# NIPCB.net
KiCad netlist of a schematic drawn in EAGLE
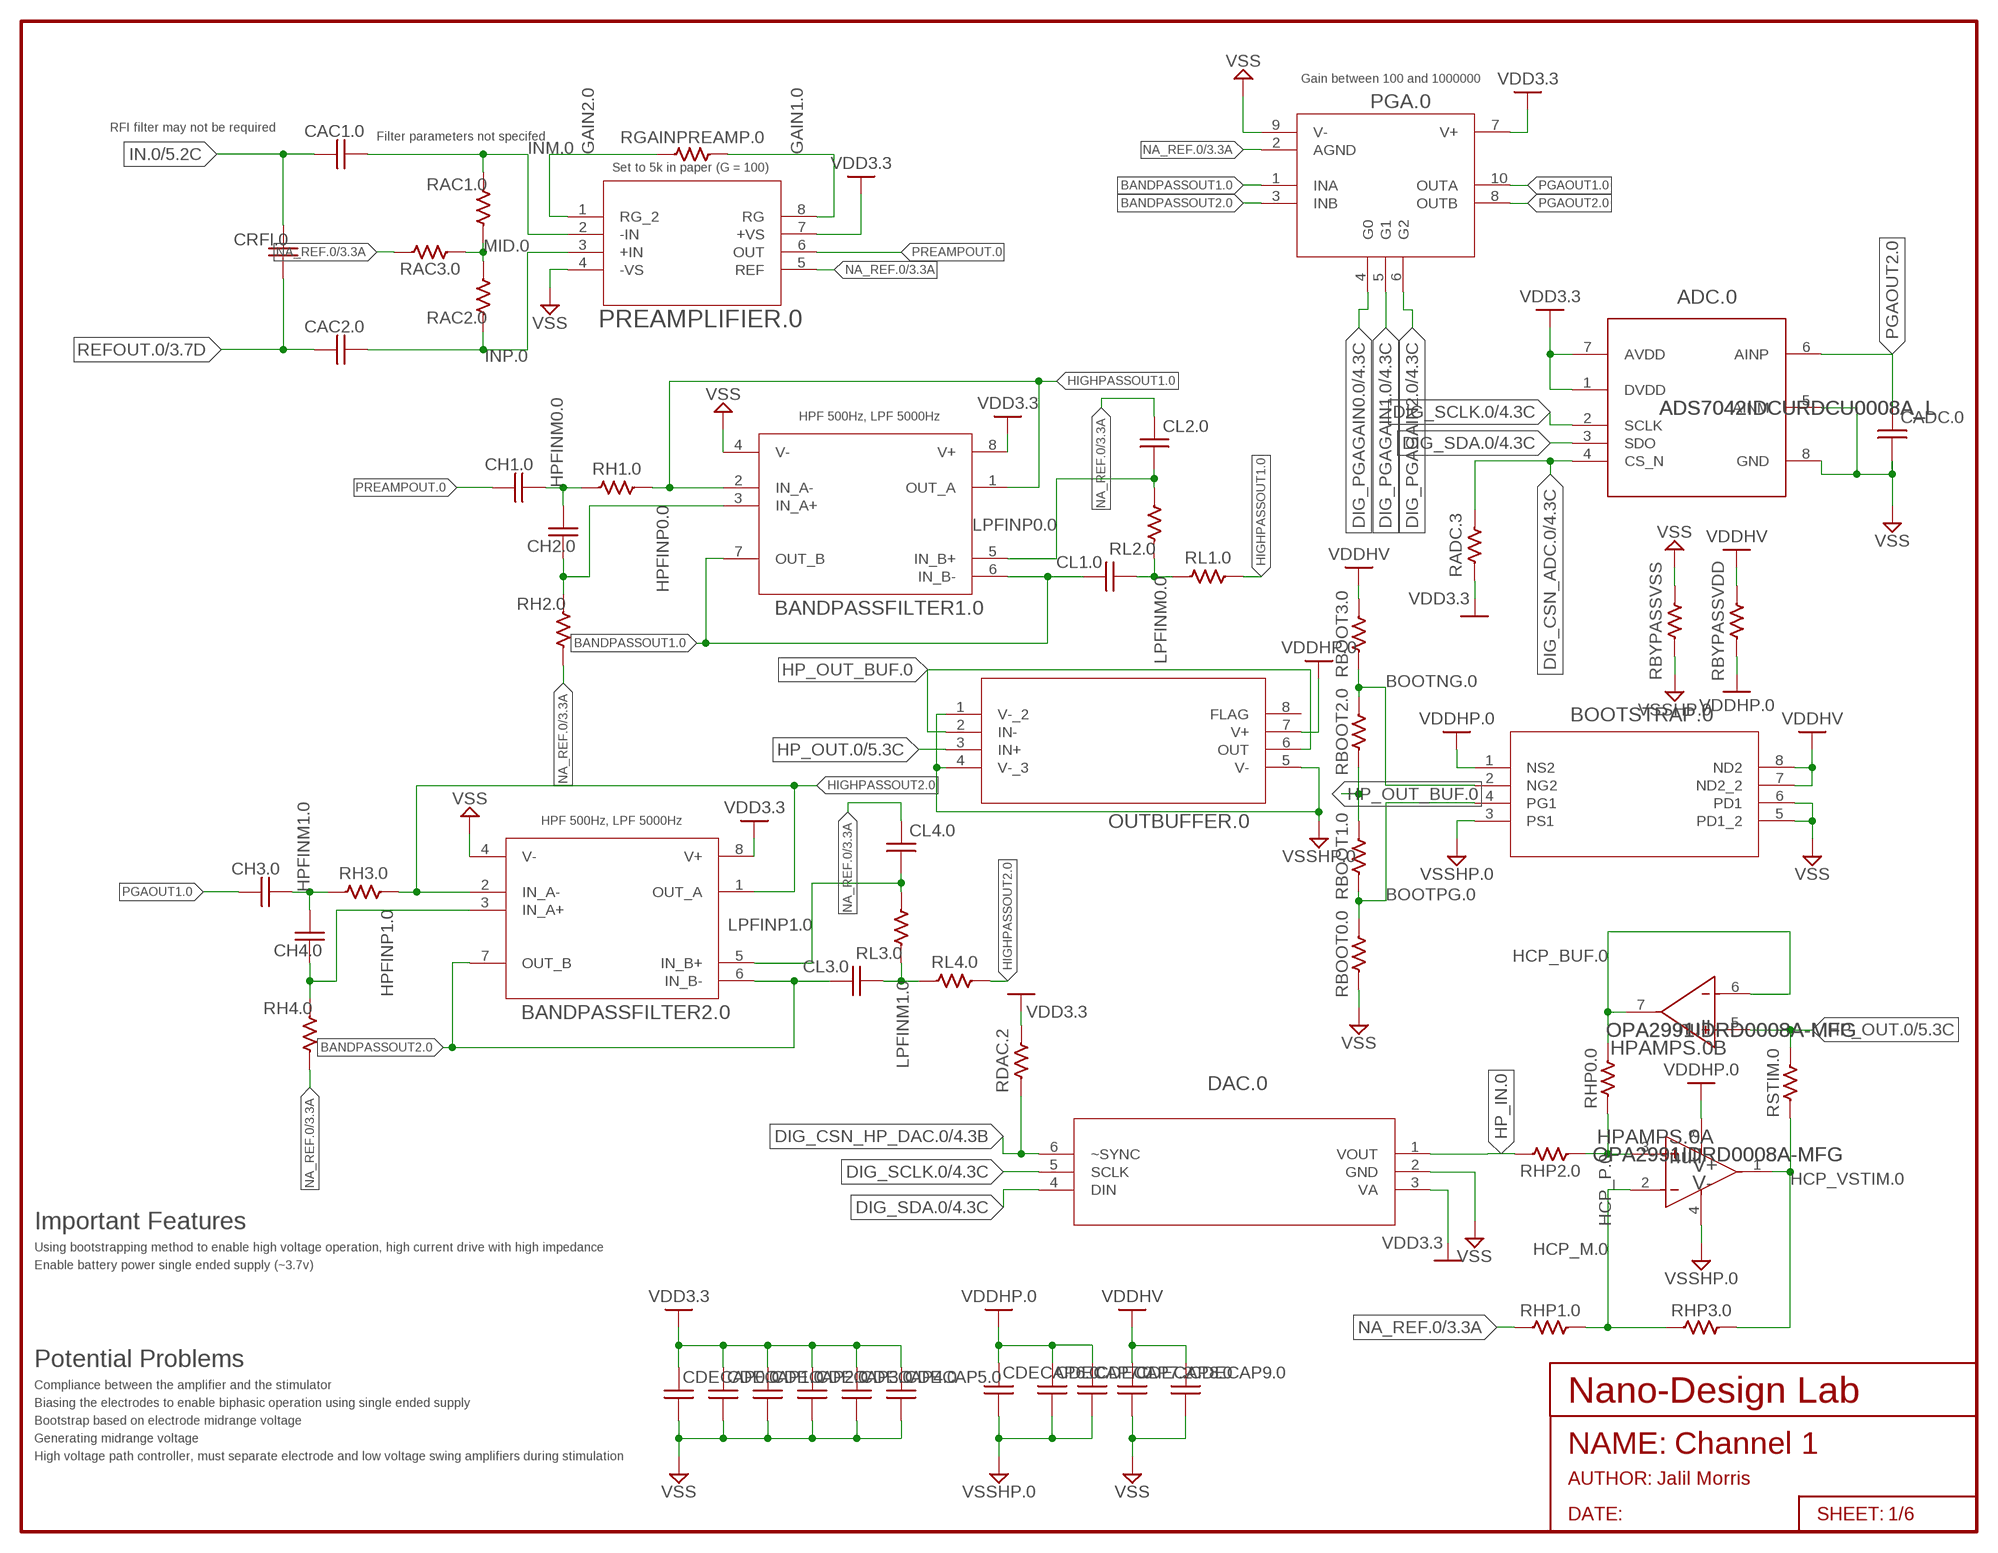
[diagram p0: schematic, sheet 1]
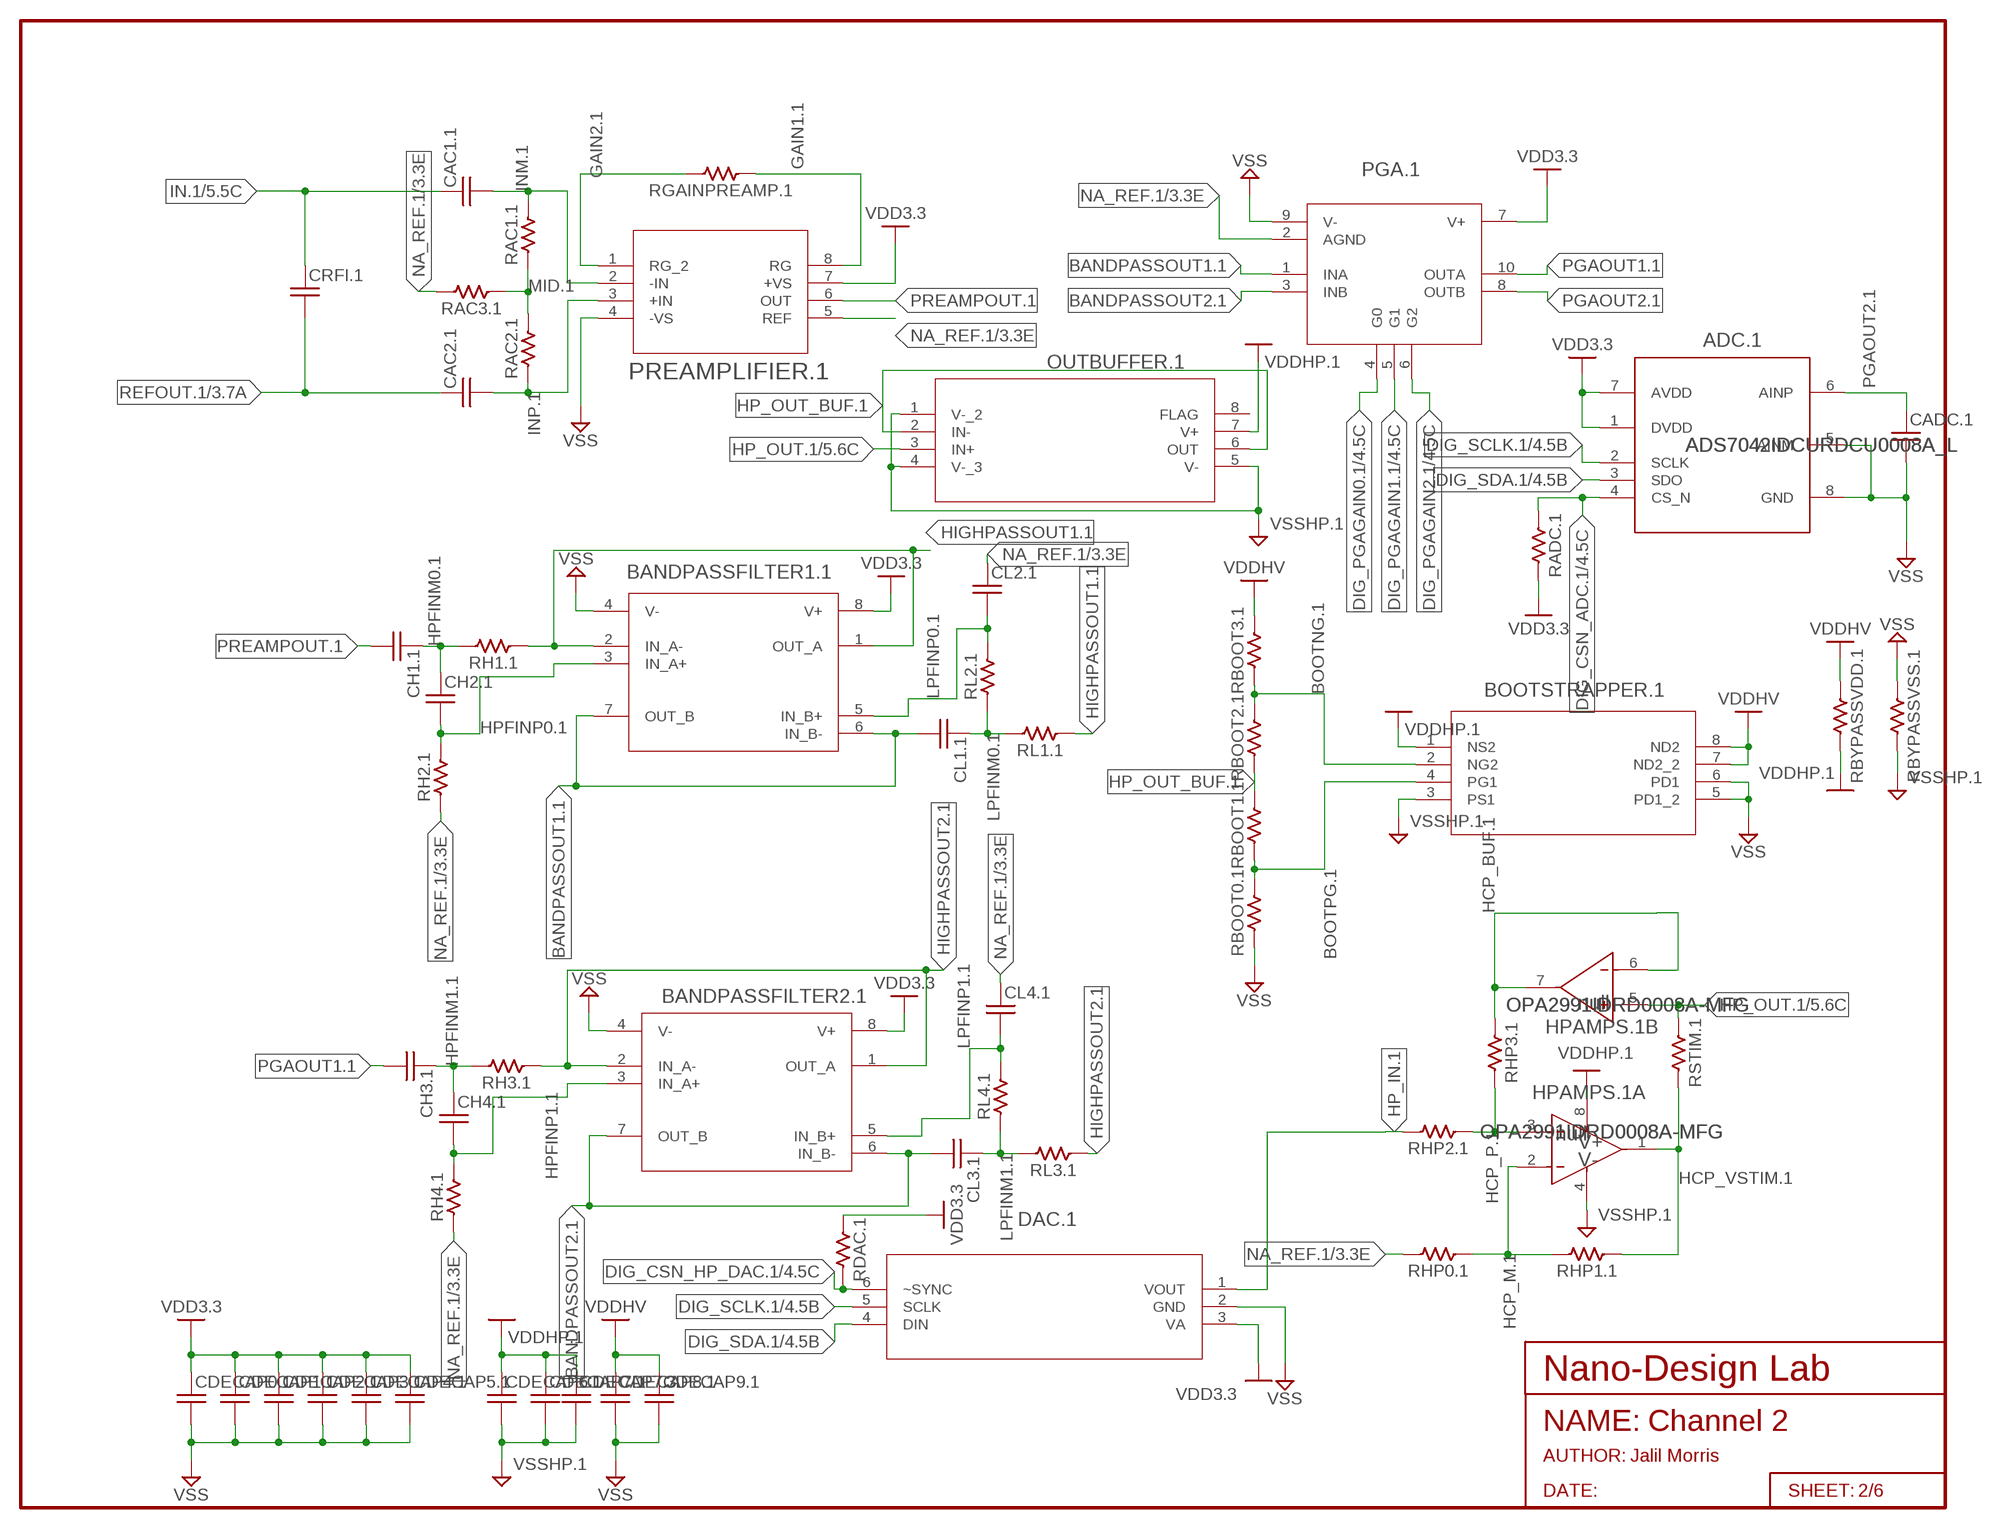
[diagram p1: schematic, sheet 2]
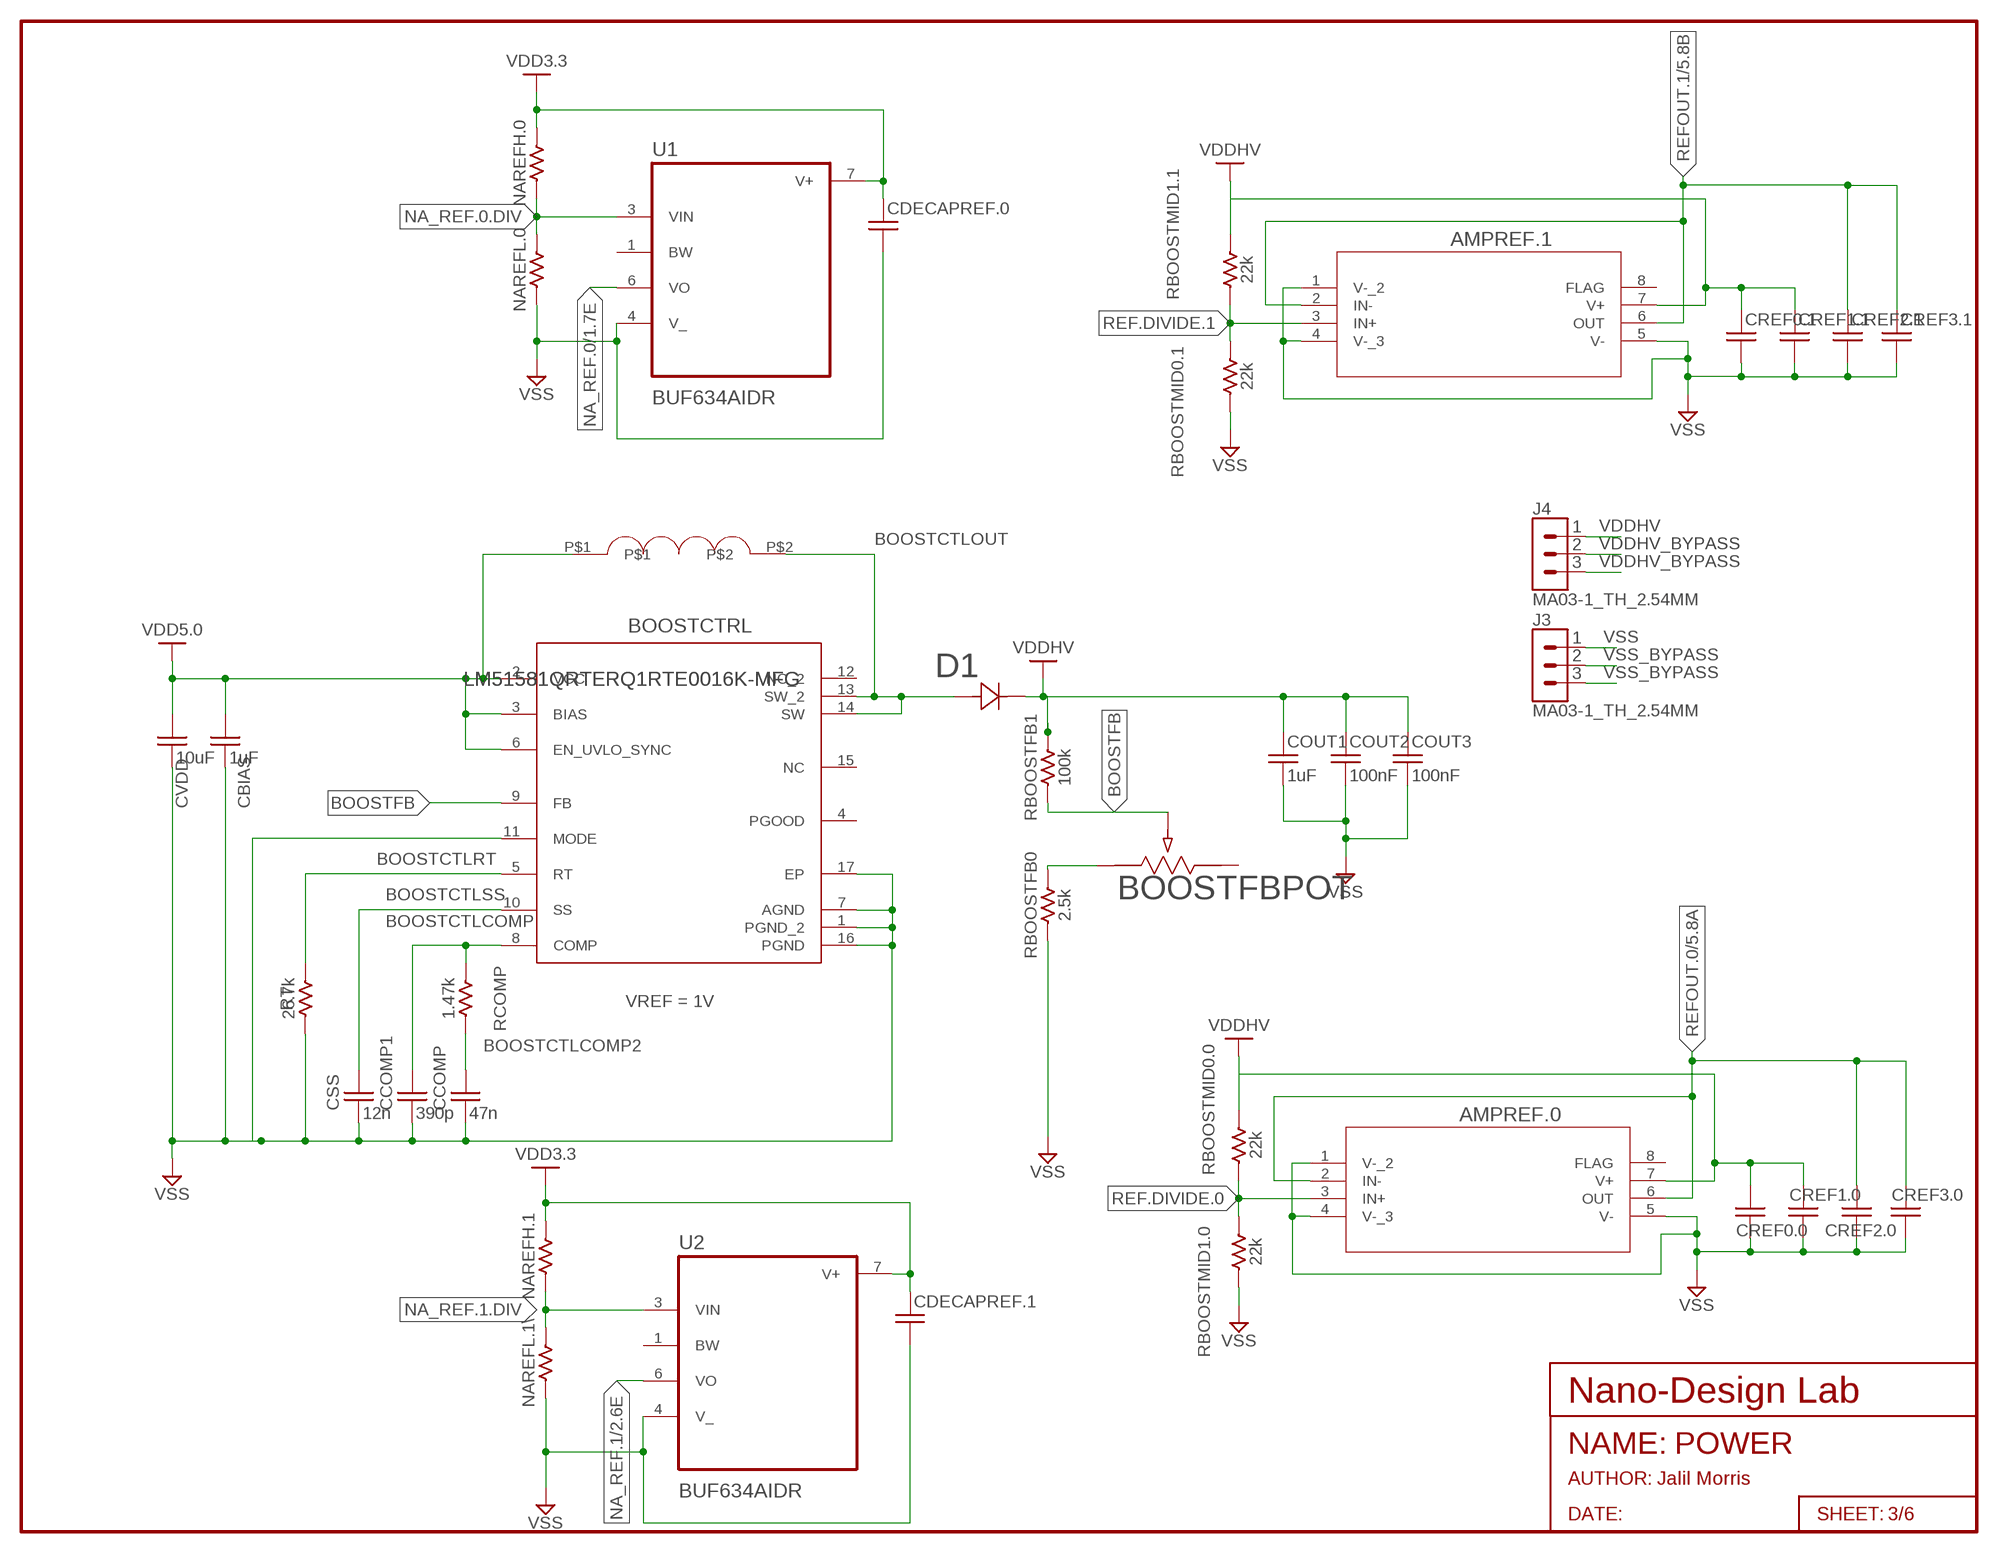
[diagram p2: schematic, sheet 3]
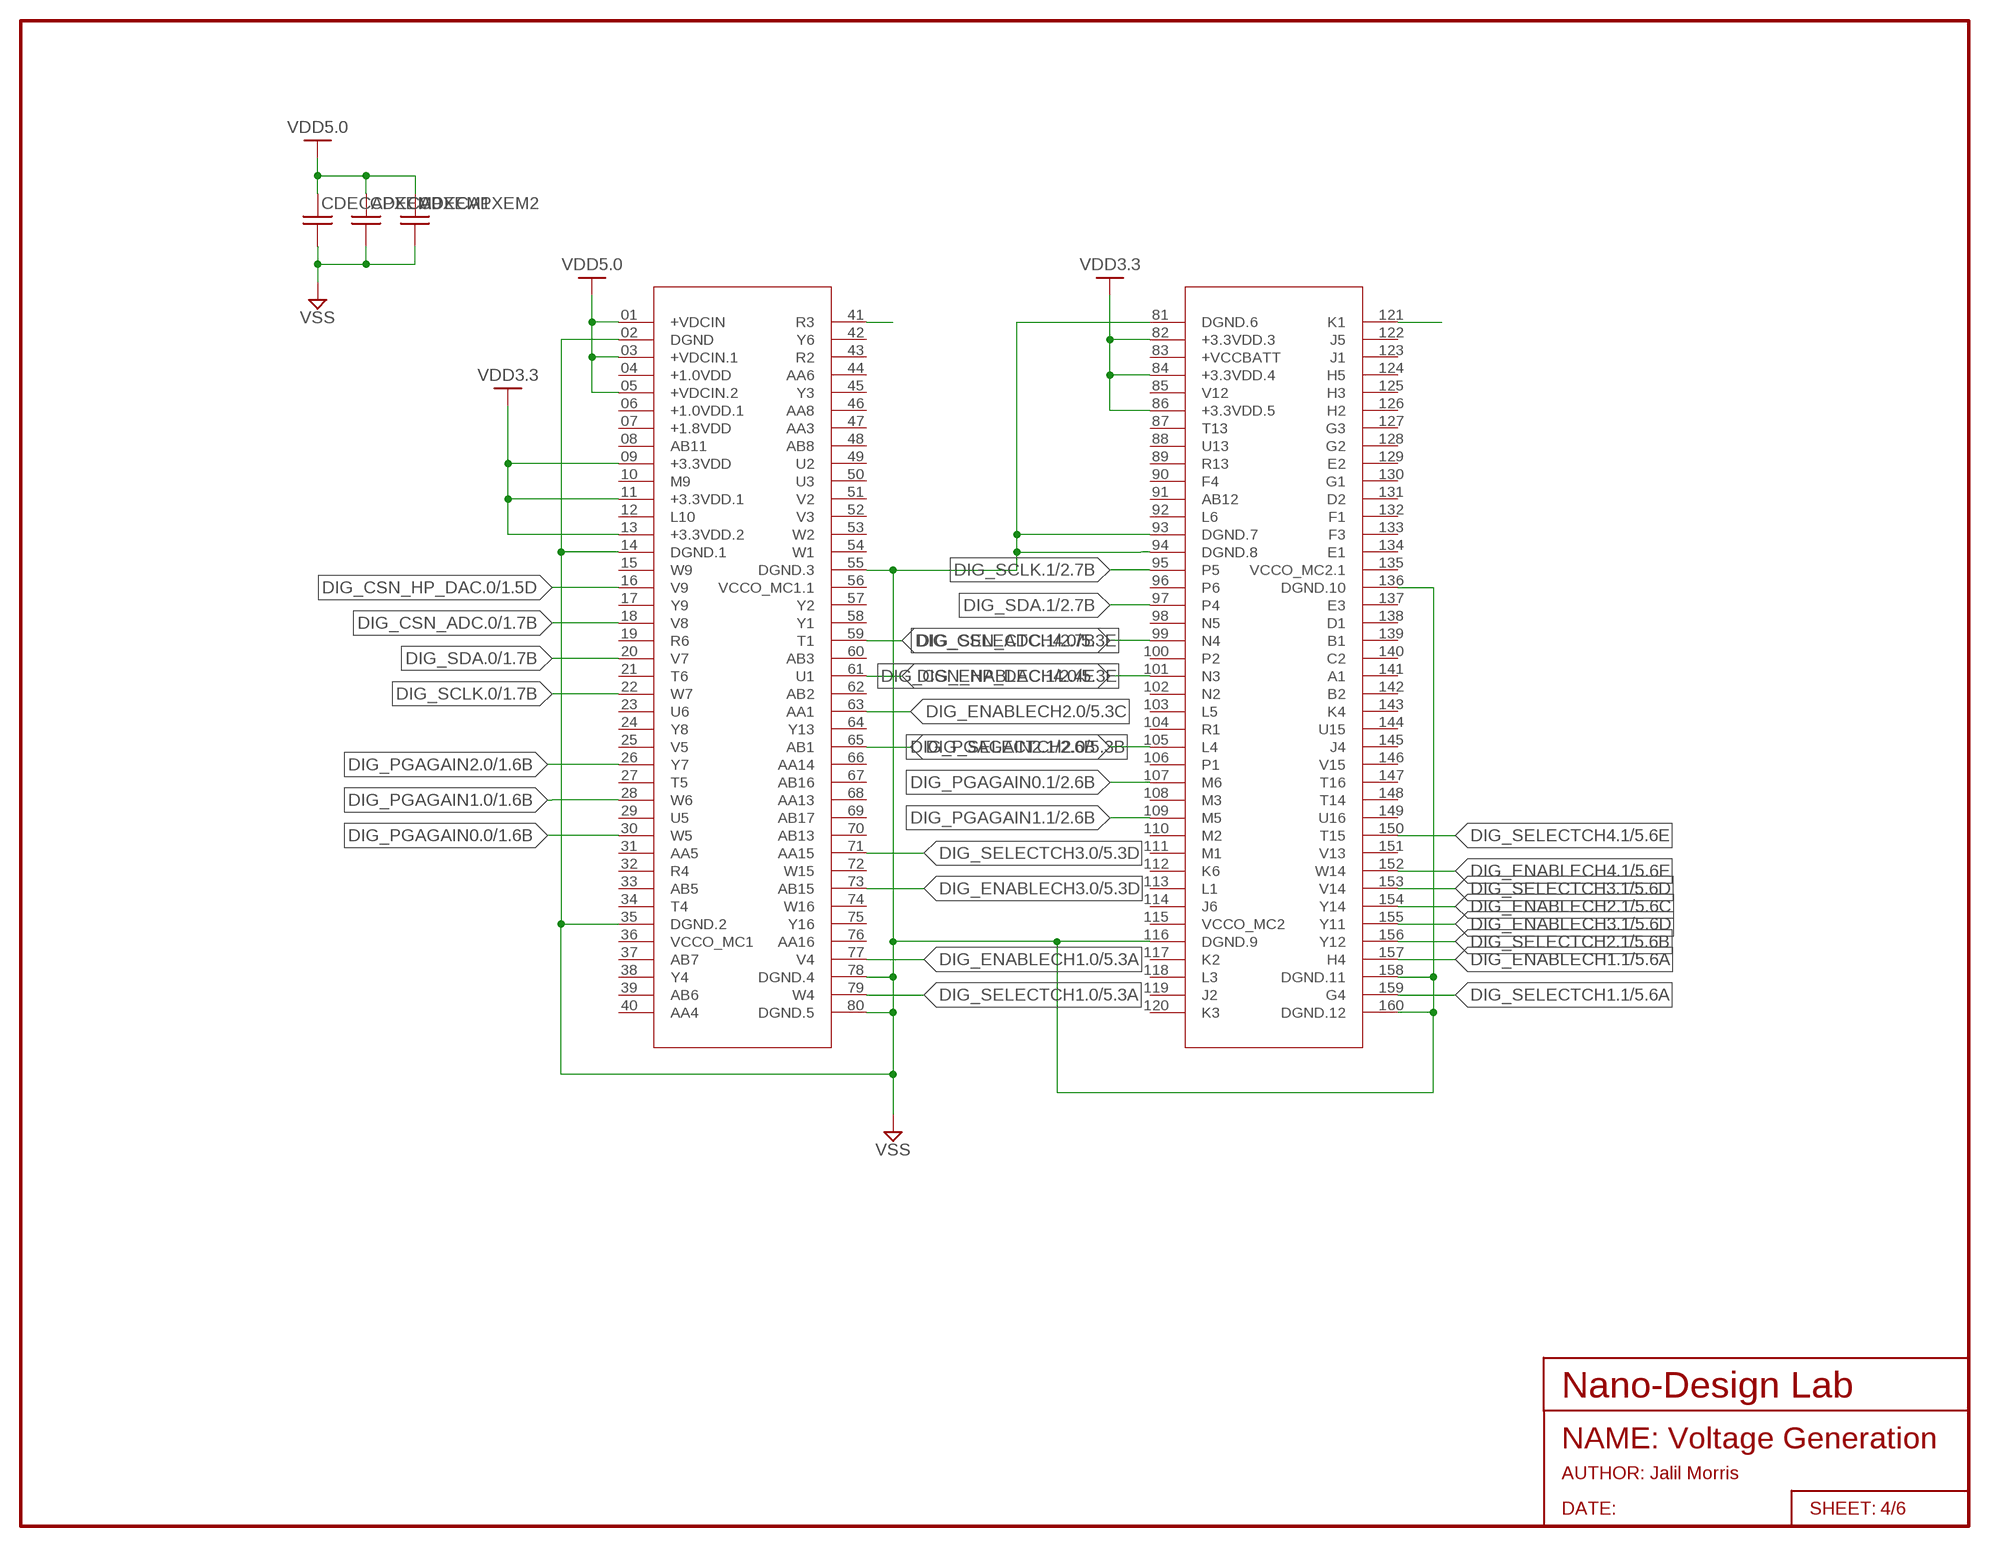
[diagram p3: schematic, sheet 4]
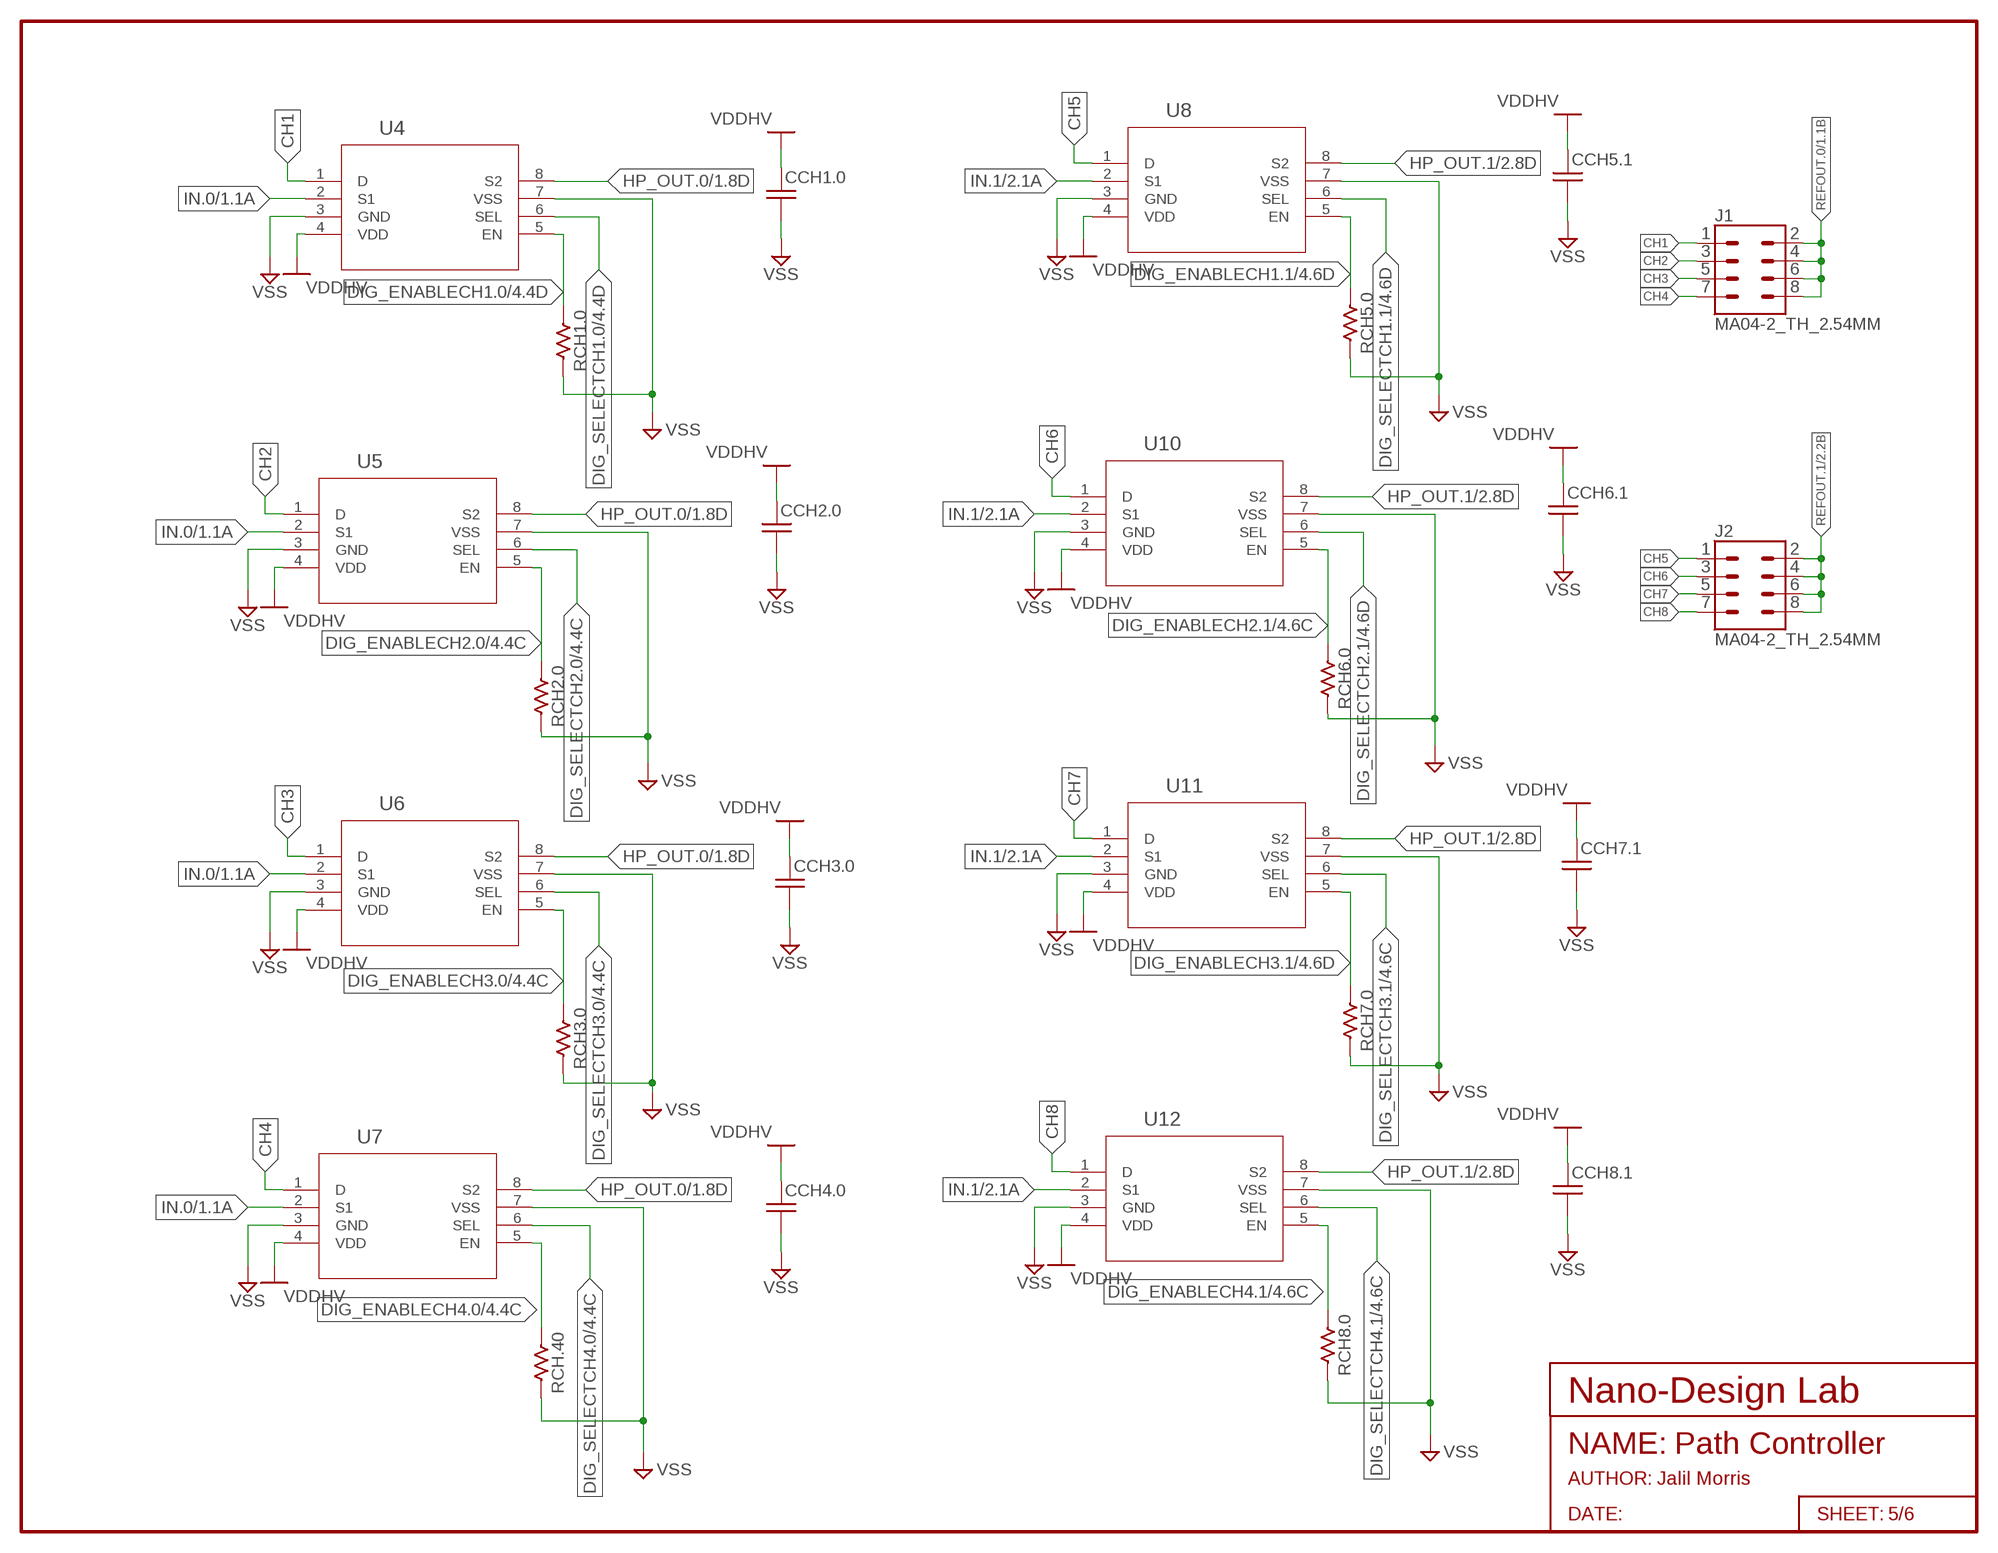
[diagram p4: schematic, sheet 5]
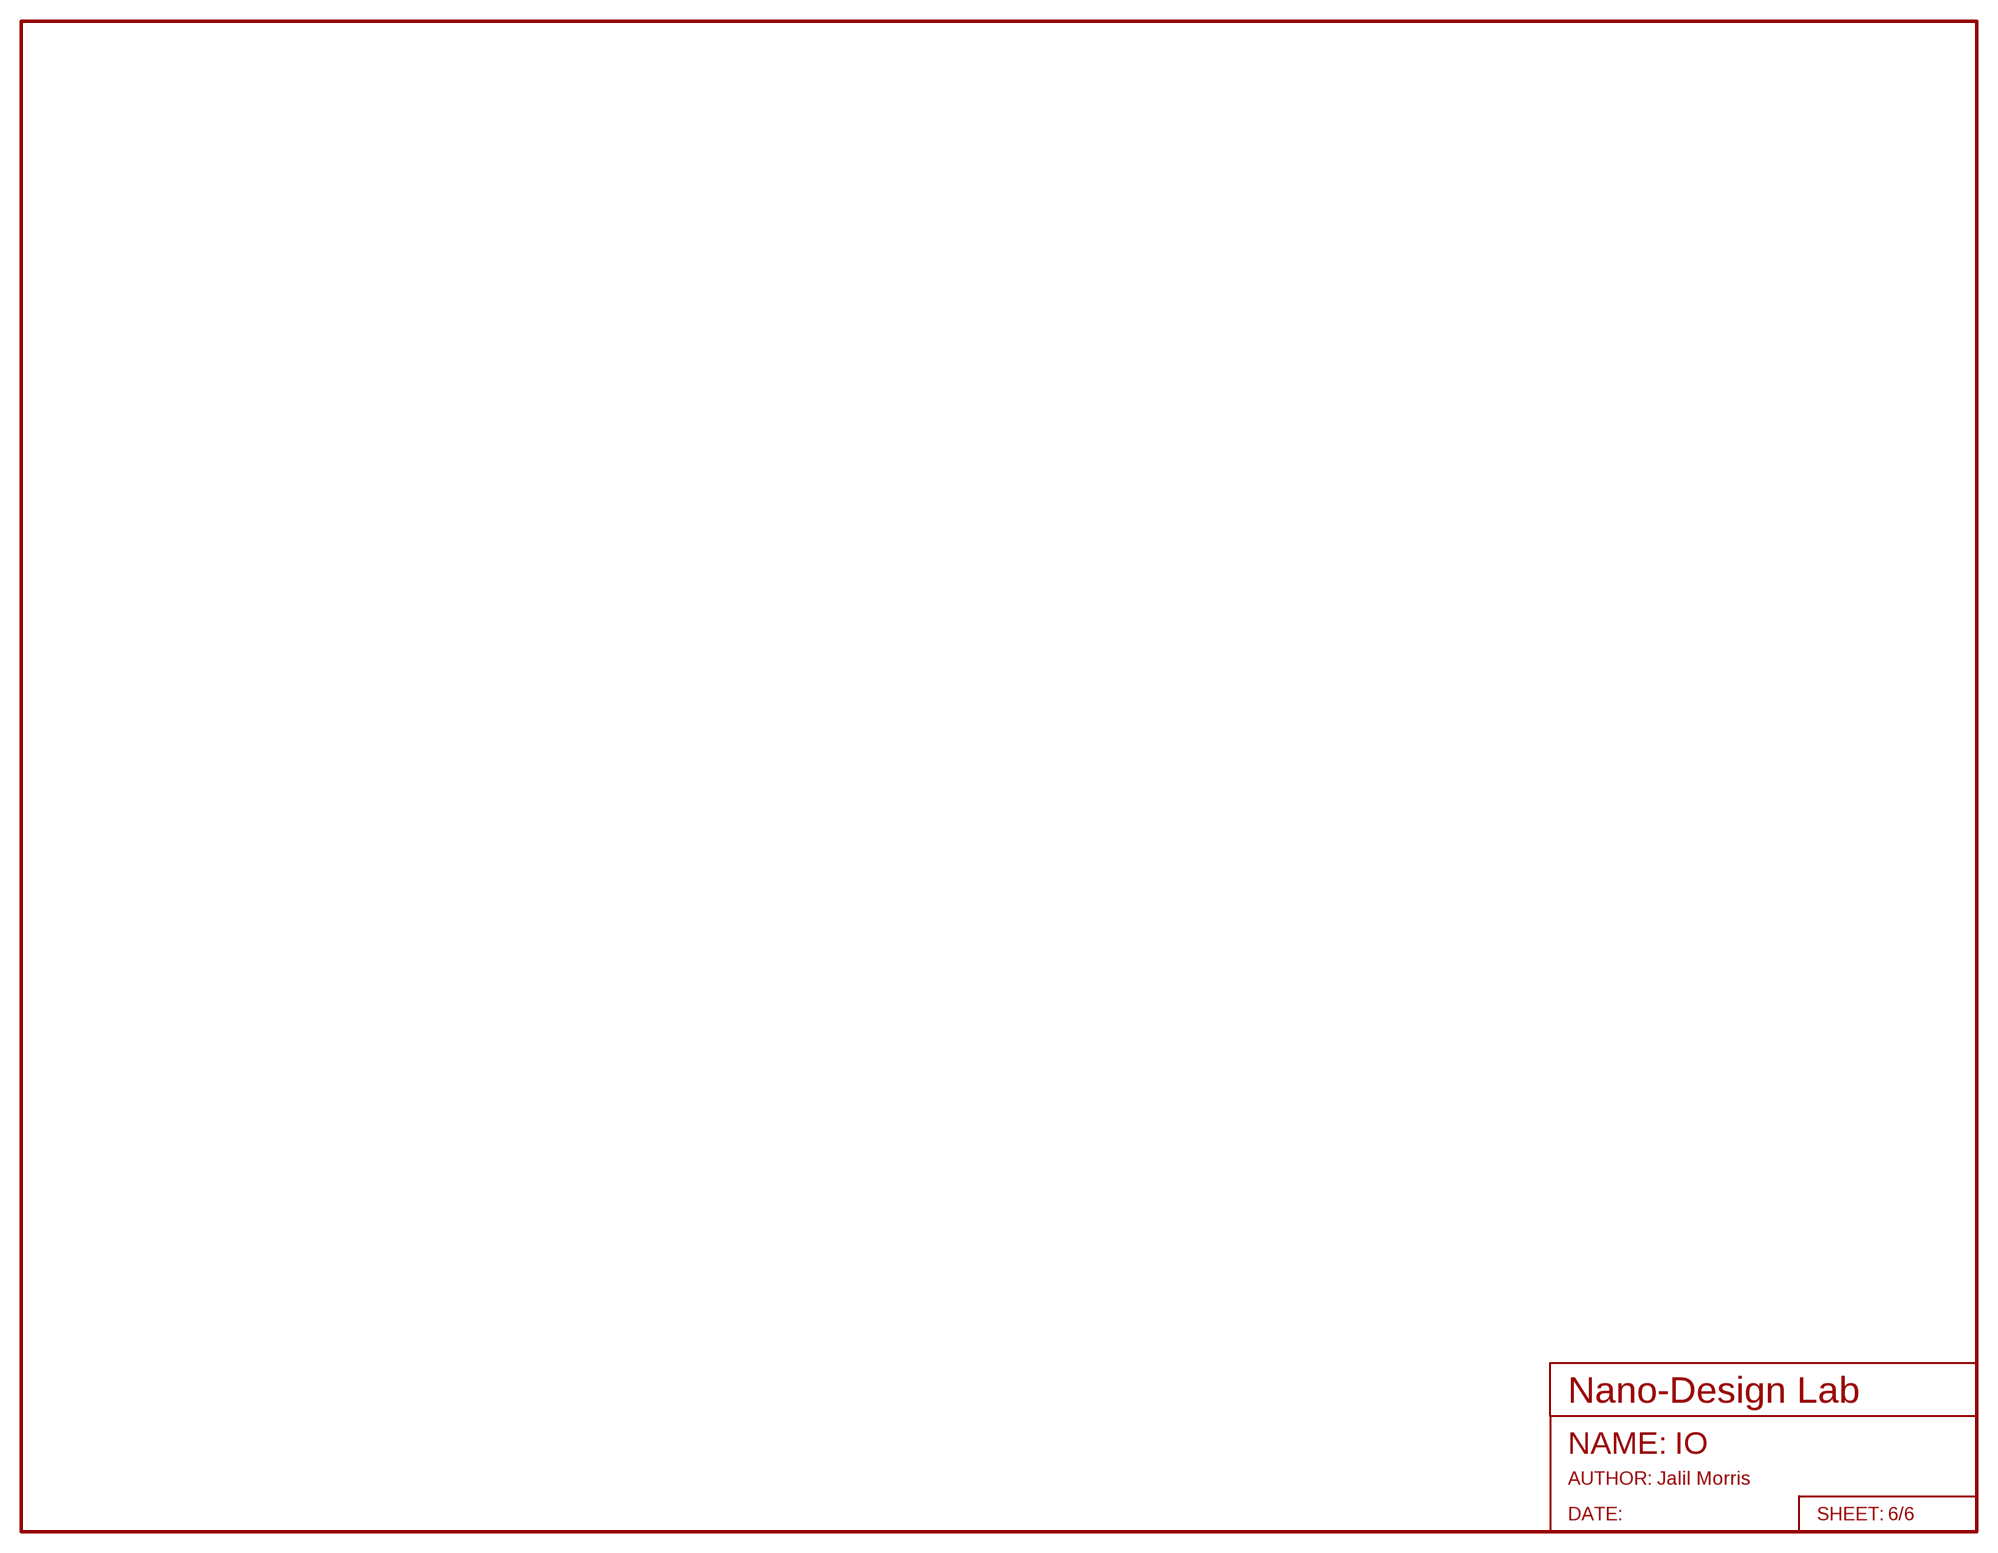
[diagram p5: schematic, sheet 6]

(export (version "E")
  (design (tool "Eeschema 10.0.6"))
  (components
    (comp (ref "ADC.0")
      (value "ADS7042IDCURDCU0008A_L")
      (footprint "eagle-import:DCU0008A_L")
      (fields
        (field (name "MANUFACTURER_PART_NUMBER") "ADS7042IDCUR")
        (field (name "COPYRIGHT") "Copyright (C) 2024 Ultra Librarian. All rights reserved.")
      )
      (libsource (lib "eagle-import") (part "ADS7042IDCURDCU0008A_L"))
    )
    (comp (ref "BANDPASSFILTER1.0")
      (value "OPA2325IDRD8_TEX")
      (footprint "eagle-import:D8_TEX")
      (fields
        (field (name "MANUFACTURER_PART_NUMBER") "OPA2325IDR")
        (field (name "COPYRIGHT") "Copyright (C) 2024 Ultra Librarian. All rights reserved.")
      )
      (libsource (lib "eagle-import") (part "OPA2325IDRD8_TEX"))
    )
    (comp (ref "BANDPASSFILTER2.0")
      (value "OPA2325IDRD8_TEX")
      (footprint "eagle-import:D8_TEX")
      (fields
        (field (name "MANUFACTURER_PART_NUMBER") "OPA2325IDR")
        (field (name "COPYRIGHT") "Copyright (C) 2024 Ultra Librarian. All rights reserved.")
      )
      (libsource (lib "eagle-import") (part "OPA2325IDRD8_TEX"))
    )
    (comp (ref "BOOTSTRAP.0")
      (value "DMC4047LSD-13SO8_DIO")
      (footprint "eagle-import:SO8_DIO")
      (fields
        (field (name "MANUFACTURER_PART_NUMBER") "DMC4047LSD-13")
        (field (name "COPYRIGHT") "Copyright (C) 2024 Ultra Librarian. All rights reserved.")
      )
      (libsource (lib "eagle-import") (part "DMC4047LSD-13SO8_DIO"))
    )
    (comp (ref "CAC1.0")
      (value "C-US0402")
      (footprint "eagle-import:0402")
      (libsource (lib "eagle-import") (part "C-US0402"))
    )
    (comp (ref "CAC2.0")
      (value "C-US0402")
      (footprint "eagle-import:0402")
      (libsource (lib "eagle-import") (part "C-US0402"))
    )
    (comp (ref "CADC.0")
      (value "C-US0402")
      (footprint "eagle-import:0402")
      (libsource (lib "eagle-import") (part "C-US0402"))
    )
    (comp (ref "CDECAP0.0")
      (value "C-US0402")
      (footprint "eagle-import:0402")
      (libsource (lib "eagle-import") (part "C-US0402"))
    )
    (comp (ref "CDECAP1.0")
      (value "C-US0402")
      (footprint "eagle-import:0402")
      (libsource (lib "eagle-import") (part "C-US0402"))
    )
    (comp (ref "CDECAP2.0")
      (value "C-US0402")
      (footprint "eagle-import:0402")
      (libsource (lib "eagle-import") (part "C-US0402"))
    )
    (comp (ref "CDECAP3.0")
      (value "C-US0402")
      (footprint "eagle-import:0402")
      (libsource (lib "eagle-import") (part "C-US0402"))
    )
    (comp (ref "CDECAP4.0")
      (value "C-US0402")
      (footprint "eagle-import:0402")
      (libsource (lib "eagle-import") (part "C-US0402"))
    )
    (comp (ref "CDECAP5.0")
      (value "C-US0402")
      (footprint "eagle-import:0402")
      (libsource (lib "eagle-import") (part "C-US0402"))
    )
    (comp (ref "CDECAP6.0")
      (value "C-US0402")
      (footprint "eagle-import:0402")
      (libsource (lib "eagle-import") (part "C-US0402"))
    )
    (comp (ref "CDECAP7.0")
      (value "C-US0402")
      (footprint "eagle-import:0402")
      (libsource (lib "eagle-import") (part "C-US0402"))
    )
    (comp (ref "CDECAP7.2")
      (value "C-US0402")
      (footprint "eagle-import:0402")
      (libsource (lib "eagle-import") (part "C-US0402"))
    )
    (comp (ref "CDECAP8.0")
      (value "C-US0402")
      (footprint "eagle-import:0402")
      (libsource (lib "eagle-import") (part "C-US0402"))
    )
    (comp (ref "CDECAP9.0")
      (value "C-US0402")
      (footprint "eagle-import:0402")
      (libsource (lib "eagle-import") (part "C-US0402"))
    )
    (comp (ref "CH1.0")
      (value "C-US0402")
      (footprint "eagle-import:0402")
      (libsource (lib "eagle-import") (part "C-US0402"))
    )
    (comp (ref "CH2.0")
      (value "C-US0402")
      (footprint "eagle-import:0402")
      (libsource (lib "eagle-import") (part "C-US0402"))
    )
    (comp (ref "CH3.0")
      (value "C-US0402")
      (footprint "eagle-import:0402")
      (libsource (lib "eagle-import") (part "C-US0402"))
    )
    (comp (ref "CH4.0")
      (value "C-US0402")
      (footprint "eagle-import:0402")
      (libsource (lib "eagle-import") (part "C-US0402"))
    )
    (comp (ref "CL1.0")
      (value "C-US0402")
      (footprint "eagle-import:0402")
      (libsource (lib "eagle-import") (part "C-US0402"))
    )
    (comp (ref "CL2.0")
      (value "C-US0402")
      (footprint "eagle-import:0402")
      (libsource (lib "eagle-import") (part "C-US0402"))
    )
    (comp (ref "CL3.0")
      (value "C-US0402")
      (footprint "eagle-import:0402")
      (libsource (lib "eagle-import") (part "C-US0402"))
    )
    (comp (ref "CL4.0")
      (value "C-US0402")
      (footprint "eagle-import:0402")
      (libsource (lib "eagle-import") (part "C-US0402"))
    )
    (comp (ref "CRFI.0")
      (value "C-US0402")
      (footprint "eagle-import:0402")
      (libsource (lib "eagle-import") (part "C-US0402"))
    )
    (comp (ref "DAC.0")
      (value "DAC081S101CIMKX/NOPBMK06A")
      (footprint "eagle-import:MK06A")
      (fields
        (field (name "MANUFACTURER_PART_NUMBER") "DAC081S101CIMKX/NOPB")
        (field (name "COPYRIGHT") "Copyright (C) 2024 Ultra Librarian. All rights reserved.")
      )
      (libsource (lib "eagle-import") (part "DAC081S101CIMKX/NOPBMK06A"))
    )
    (comp (ref "HPAMPS.0")
      (value "OPA2991IDRD0008A-MFG")
      (footprint "eagle-import:D0008A-MFG")
      (fields
        (field (name "MANUFACTURER_PART_NUMBER") "OPA2991IDR")
        (field (name "COPYRIGHT") "Copyright (C) 2024 Ultra Librarian. All rights reserved.")
      )
      (libsource (lib "eagle-import") (part "OPA2991IDRD0008A-MFG"))
    )
    (comp (ref "OUTBUFFER.0")
      (value "OPA552UA/2K5D8")
      (footprint "eagle-import:D8")
      (fields
        (field (name "MANUFACTURER_PART_NUMBER") "OPA552UA/2K5")
        (field (name "COPYRIGHT") "Copyright (C) 2024 Ultra Librarian. All rights reserved.")
      )
      (libsource (lib "eagle-import") (part "OPA552UA/2K5D8"))
    )
    (comp (ref "PGA.0")
      (value "LTC6911CMS-1TRPBFMSOP-10_MS_LIT")
      (footprint "eagle-import:MSOP-10_MS_LIT")
      (fields
        (field (name "MANUFACTURER_PART_NUMBER") "LTC6911CMS-1#TRPBF")
        (field (name "COPYRIGHT") "Copyright (C) 2024 Ultra Librarian. All rights reserved.")
      )
      (libsource (lib "eagle-import") (part "LTC6911CMS-1TRPBFMSOP-10_MS_LIT"))
    )
    (comp (ref "PREAMPLIFIER.0")
      (value "INA818IDSOIC-8_TEX")
      (footprint "eagle-import:SOIC-8_TEX")
      (fields
        (field (name "MANUFACTURER_PART_NUMBER") "INA818ID")
        (field (name "COPYRIGHT") "Copyright (C) 2024 Ultra Librarian. All rights reserved.")
      )
      (libsource (lib "eagle-import") (part "INA818IDSOIC-8_TEX"))
    )
    (comp (ref "RAC1.0")
      (value "R-US0402")
      (footprint "eagle-import:0402")
      (libsource (lib "eagle-import") (part "R-US0402"))
    )
    (comp (ref "RAC2.0")
      (value "R-US0402")
      (footprint "eagle-import:0402")
      (libsource (lib "eagle-import") (part "R-US0402"))
    )
    (comp (ref "RAC3.0")
      (value "R-US0402")
      (footprint "eagle-import:0402")
      (libsource (lib "eagle-import") (part "R-US0402"))
    )
    (comp (ref "RADC.3")
      (value "R-US0402")
      (footprint "eagle-import:0402")
      (libsource (lib "eagle-import") (part "R-US0402"))
    )
    (comp (ref "RBOOT0.0")
      (value "R-US0603")
      (footprint "eagle-import:0603")
      (libsource (lib "eagle-import") (part "esbd-passives_vf.aVnswyxgQrGgV-hLEV-kMQ_R-US0603"))
    )
    (comp (ref "RBOOT1.0")
      (value "R-US0603")
      (footprint "eagle-import:0603")
      (libsource (lib "eagle-import") (part "esbd-passives_vf.aVnswyxgQrGgV-hLEV-kMQ_R-US0603"))
    )
    (comp (ref "RBOOT2.0")
      (value "R-US0603")
      (footprint "eagle-import:0603")
      (libsource (lib "eagle-import") (part "esbd-passives_vf.aVnswyxgQrGgV-hLEV-kMQ_R-US0603"))
    )
    (comp (ref "RBOOT3.0")
      (value "R-US0603")
      (footprint "eagle-import:0603")
      (libsource (lib "eagle-import") (part "esbd-passives_vf.aVnswyxgQrGgV-hLEV-kMQ_R-US0603"))
    )
    (comp (ref "RBYPASSVDD")
      (value "R-US0402")
      (footprint "eagle-import:0402")
      (libsource (lib "eagle-import") (part "R-US0402"))
    )
    (comp (ref "RBYPASSVSS")
      (value "R-US0402")
      (footprint "eagle-import:0402")
      (libsource (lib "eagle-import") (part "R-US0402"))
    )
    (comp (ref "RDAC.2")
      (value "R-US0402")
      (footprint "eagle-import:0402")
      (libsource (lib "eagle-import") (part "R-US0402"))
    )
    (comp (ref "RGAINPREAMP.0")
      (value "R-US0402")
      (footprint "eagle-import:0402")
      (libsource (lib "eagle-import") (part "R-US0402"))
    )
    (comp (ref "RH1.0")
      (value "R-US0402")
      (footprint "eagle-import:0402")
      (libsource (lib "eagle-import") (part "R-US0402"))
    )
    (comp (ref "RH2.0")
      (value "R-US0402")
      (footprint "eagle-import:0402")
      (libsource (lib "eagle-import") (part "R-US0402"))
    )
    (comp (ref "RH3.0")
      (value "R-US0402")
      (footprint "eagle-import:0402")
      (libsource (lib "eagle-import") (part "R-US0402"))
    )
    (comp (ref "RH4.0")
      (value "R-US0402")
      (footprint "eagle-import:0402")
      (libsource (lib "eagle-import") (part "R-US0402"))
    )
    (comp (ref "RHP0.0")
      (value "R-US0603")
      (footprint "eagle-import:0603")
      (libsource (lib "eagle-import") (part "esbd-passives_vf.aVnswyxgQrGgV-hLEV-kMQ_R-US0603"))
    )
    (comp (ref "RHP1.0")
      (value "R-US0603")
      (footprint "eagle-import:0603")
      (libsource (lib "eagle-import") (part "esbd-passives_vf.aVnswyxgQrGgV-hLEV-kMQ_R-US0603"))
    )
    (comp (ref "RHP2.0")
      (value "R-US0603")
      (footprint "eagle-import:0603")
      (libsource (lib "eagle-import") (part "esbd-passives_vf.aVnswyxgQrGgV-hLEV-kMQ_R-US0603"))
    )
    (comp (ref "RHP3.0")
      (value "R-US0603")
      (footprint "eagle-import:0603")
      (libsource (lib "eagle-import") (part "esbd-passives_vf.aVnswyxgQrGgV-hLEV-kMQ_R-US0603"))
    )
    (comp (ref "RL1.0")
      (value "R-US0402")
      (footprint "eagle-import:0402")
      (libsource (lib "eagle-import") (part "R-US0402"))
    )
    (comp (ref "RL2.0")
      (value "R-US0402")
      (footprint "eagle-import:0402")
      (libsource (lib "eagle-import") (part "R-US0402"))
    )
    (comp (ref "RL3.0")
      (value "R-US0402")
      (footprint "eagle-import:0402")
      (libsource (lib "eagle-import") (part "R-US0402"))
    )
    (comp (ref "RL4.0")
      (value "R-US0402")
      (footprint "eagle-import:0402")
      (libsource (lib "eagle-import") (part "R-US0402"))
    )
    (comp (ref "RSTIM.0")
      (value "R-US0603")
      (footprint "eagle-import:0603")
      (libsource (lib "eagle-import") (part "esbd-passives_vf.aVnswyxgQrGgV-hLEV-kMQ_R-US0603"))
    )
    (comp (ref "CDECAPXEM0")
      (value "C-US0805")
      (footprint "eagle-import:0805")
      (libsource (lib "eagle-import") (part "C-US0805"))
    )
    (comp (ref "CDECAPXEM1")
      (value "C-US0603")
      (footprint "eagle-import:0603")
      (libsource (lib "eagle-import") (part "C-US0603"))
    )
    (comp (ref "CDECAPXEM2")
      (value "C-US0603")
      (footprint "eagle-import:0603")
      (libsource (lib "eagle-import") (part "C-US0603"))
    )
    (comp (ref "U$2")
      (value "XEM7310")
      (footprint "eagle-import:XEM7310")
      (libsource (lib "eagle-import") (part "XEM7310"))
    )
    (comp (ref "CCH1.0")
      (value "C-US0402")
      (footprint "eagle-import:0402")
      (libsource (lib "eagle-import") (part "esbd-passives_vf.aVnswyxgQrGgV-hLEV-kMQ_C-US0402"))
    )
    (comp (ref "CCH2.0")
      (value "C-US0402")
      (footprint "eagle-import:0402")
      (libsource (lib "eagle-import") (part "esbd-passives_vf.aVnswyxgQrGgV-hLEV-kMQ_C-US0402"))
    )
    (comp (ref "CCH3.0")
      (value "C-US0402")
      (footprint "eagle-import:0402")
      (libsource (lib "eagle-import") (part "esbd-passives_vf.aVnswyxgQrGgV-hLEV-kMQ_C-US0402"))
    )
    (comp (ref "CCH4.0")
      (value "C-US0402")
      (footprint "eagle-import:0402")
      (libsource (lib "eagle-import") (part "esbd-passives_vf.aVnswyxgQrGgV-hLEV-kMQ_C-US0402"))
    )
    (comp (ref "CCH5.1")
      (value "C-US0402")
      (footprint "eagle-import:0402")
      (libsource (lib "eagle-import") (part "esbd-passives_vf.aVnswyxgQrGgV-hLEV-kMQ_C-US0402"))
    )
    (comp (ref "CCH6.1")
      (value "C-US0402")
      (footprint "eagle-import:0402")
      (libsource (lib "eagle-import") (part "esbd-passives_vf.aVnswyxgQrGgV-hLEV-kMQ_C-US0402"))
    )
    (comp (ref "CCH7.1")
      (value "C-US0402")
      (footprint "eagle-import:0402")
      (libsource (lib "eagle-import") (part "esbd-passives_vf.aVnswyxgQrGgV-hLEV-kMQ_C-US0402"))
    )
    (comp (ref "CCH8.1")
      (value "C-US0402")
      (footprint "eagle-import:0402")
      (libsource (lib "eagle-import") (part "esbd-passives_vf.aVnswyxgQrGgV-hLEV-kMQ_C-US0402"))
    )
    (comp (ref "J1")
      (value "MA04-2_TH_2.54MM")
      (footprint "eagle-import:MA04-2_TH_2.54MM")
      (libsource (lib "eagle-import") (part "MA04-2_TH_2.54MM"))
    )
    (comp (ref "J2")
      (value "MA04-2_TH_2.54MM")
      (footprint "eagle-import:MA04-2_TH_2.54MM")
      (libsource (lib "eagle-import") (part "MA04-2_TH_2.54MM"))
    )
    (comp (ref "RCH.40")
      (value "R-US0402")
      (footprint "eagle-import:0402")
      (libsource (lib "eagle-import") (part "esbd-passives_vf.aVnswyxgQrGgV-hLEV-kMQ_R-US0402"))
    )
    (comp (ref "RCH1.0")
      (value "R-US0402")
      (footprint "eagle-import:0402")
      (libsource (lib "eagle-import") (part "esbd-passives_vf.aVnswyxgQrGgV-hLEV-kMQ_R-US0402"))
    )
    (comp (ref "RCH2.0")
      (value "R-US0402")
      (footprint "eagle-import:0402")
      (libsource (lib "eagle-import") (part "esbd-passives_vf.aVnswyxgQrGgV-hLEV-kMQ_R-US0402"))
    )
    (comp (ref "RCH3.0")
      (value "R-US0402")
      (footprint "eagle-import:0402")
      (libsource (lib "eagle-import") (part "esbd-passives_vf.aVnswyxgQrGgV-hLEV-kMQ_R-US0402"))
    )
    (comp (ref "RCH5.0")
      (value "R-US0402")
      (footprint "eagle-import:0402")
      (libsource (lib "eagle-import") (part "esbd-passives_vf.aVnswyxgQrGgV-hLEV-kMQ_R-US0402"))
    )
    (comp (ref "RCH6.0")
      (value "R-US0402")
      (footprint "eagle-import:0402")
      (libsource (lib "eagle-import") (part "esbd-passives_vf.aVnswyxgQrGgV-hLEV-kMQ_R-US0402"))
    )
    (comp (ref "RCH7.0")
      (value "R-US0402")
      (footprint "eagle-import:0402")
      (libsource (lib "eagle-import") (part "esbd-passives_vf.aVnswyxgQrGgV-hLEV-kMQ_R-US0402"))
    )
    (comp (ref "RCH8.0")
      (value "R-US0402")
      (footprint "eagle-import:0402")
      (libsource (lib "eagle-import") (part "esbd-passives_vf.aVnswyxgQrGgV-hLEV-kMQ_R-US0402"))
    )
    (comp (ref "U4")
      (value "TMUX7219DGKRVSSOP_9DGKR_TEX")
      (footprint "eagle-import:VSSOP_9DGKR_TEX")
      (fields
        (field (name "MANUFACTURER_PART_NUMBER") "TMUX7219DGKR")
        (field (name "COPYRIGHT") "Copyright (C) 2024 Ultra Librarian. All rights reserved.")
      )
      (libsource (lib "eagle-import") (part "TMUX7219DGKRVSSOP_9DGKR_TEX"))
    )
    (comp (ref "U5")
      (value "TMUX7219DGKRVSSOP_9DGKR_TEX")
      (footprint "eagle-import:VSSOP_9DGKR_TEX")
      (fields
        (field (name "MANUFACTURER_PART_NUMBER") "TMUX7219DGKR")
        (field (name "COPYRIGHT") "Copyright (C) 2024 Ultra Librarian. All rights reserved.")
      )
      (libsource (lib "eagle-import") (part "TMUX7219DGKRVSSOP_9DGKR_TEX"))
    )
    (comp (ref "U6")
      (value "TMUX7219DGKRVSSOP_9DGKR_TEX")
      (footprint "eagle-import:VSSOP_9DGKR_TEX")
      (fields
        (field (name "MANUFACTURER_PART_NUMBER") "TMUX7219DGKR")
        (field (name "COPYRIGHT") "Copyright (C) 2024 Ultra Librarian. All rights reserved.")
      )
      (libsource (lib "eagle-import") (part "TMUX7219DGKRVSSOP_9DGKR_TEX"))
    )
    (comp (ref "U7")
      (value "TMUX7219DGKRVSSOP_9DGKR_TEX")
      (footprint "eagle-import:VSSOP_9DGKR_TEX")
      (fields
        (field (name "MANUFACTURER_PART_NUMBER") "TMUX7219DGKR")
        (field (name "COPYRIGHT") "Copyright (C) 2024 Ultra Librarian. All rights reserved.")
      )
      (libsource (lib "eagle-import") (part "TMUX7219DGKRVSSOP_9DGKR_TEX"))
    )
    (comp (ref "U8")
      (value "TMUX7219DGKRVSSOP_9DGKR_TEX")
      (footprint "eagle-import:VSSOP_9DGKR_TEX")
      (fields
        (field (name "MANUFACTURER_PART_NUMBER") "TMUX7219DGKR")
        (field (name "COPYRIGHT") "Copyright (C) 2024 Ultra Librarian. All rights reserved.")
      )
      (libsource (lib "eagle-import") (part "TMUX7219DGKRVSSOP_9DGKR_TEX"))
    )
    (comp (ref "U10")
      (value "TMUX7219DGKRVSSOP_9DGKR_TEX")
      (footprint "eagle-import:VSSOP_9DGKR_TEX")
      (fields
        (field (name "MANUFACTURER_PART_NUMBER") "TMUX7219DGKR")
        (field (name "COPYRIGHT") "Copyright (C) 2024 Ultra Librarian. All rights reserved.")
      )
      (libsource (lib "eagle-import") (part "TMUX7219DGKRVSSOP_9DGKR_TEX"))
    )
    (comp (ref "U11")
      (value "TMUX7219DGKRVSSOP_9DGKR_TEX")
      (footprint "eagle-import:VSSOP_9DGKR_TEX")
      (fields
        (field (name "MANUFACTURER_PART_NUMBER") "TMUX7219DGKR")
        (field (name "COPYRIGHT") "Copyright (C) 2024 Ultra Librarian. All rights reserved.")
      )
      (libsource (lib "eagle-import") (part "TMUX7219DGKRVSSOP_9DGKR_TEX"))
    )
    (comp (ref "U12")
      (value "TMUX7219DGKRVSSOP_9DGKR_TEX")
      (footprint "eagle-import:VSSOP_9DGKR_TEX")
      (fields
        (field (name "MANUFACTURER_PART_NUMBER") "TMUX7219DGKR")
        (field (name "COPYRIGHT") "Copyright (C) 2024 Ultra Librarian. All rights reserved.")
      )
      (libsource (lib "eagle-import") (part "TMUX7219DGKRVSSOP_9DGKR_TEX"))
    )
    (comp (ref "ADC.1")
      (value "ADS7042IDCURDCU0008A_L")
      (footprint "eagle-import:DCU0008A_L")
      (fields
        (field (name "MANUFACTURER_PART_NUMBER") "ADS7042IDCUR")
        (field (name "COPYRIGHT") "Copyright (C) 2024 Ultra Librarian. All rights reserved.")
      )
      (libsource (lib "eagle-import") (part "ADS7042IDCURDCU0008A_L"))
    )
    (comp (ref "BANDPASSFILTER1.1")
      (value "OPA2325IDRD8_TEX-L")
      (footprint "eagle-import:D8_TEX-L")
      (fields
        (field (name "MANUFACTURER_PART_NUMBER") "OPA2325IDR")
        (field (name "COPYRIGHT") "Copyright (C) 2024 Ultra Librarian. All rights reserved.")
      )
      (libsource (lib "eagle-import") (part "OPA2325IDRD8_TEX-L"))
    )
    (comp (ref "BANDPASSFILTER2.1")
      (value "OPA2325IDRD8_TEX-L")
      (footprint "eagle-import:D8_TEX-L")
      (fields
        (field (name "MANUFACTURER_PART_NUMBER") "OPA2325IDR")
        (field (name "COPYRIGHT") "Copyright (C) 2024 Ultra Librarian. All rights reserved.")
      )
      (libsource (lib "eagle-import") (part "OPA2325IDRD8_TEX-L"))
    )
    (comp (ref "BOOTSTRAPPER.1")
      (value "DMC4047LSD-13SO8_DIO")
      (footprint "eagle-import:SO8_DIO")
      (fields
        (field (name "MANUFACTURER_PART_NUMBER") "DMC4047LSD-13")
        (field (name "COPYRIGHT") "Copyright (C) 2024 Ultra Librarian. All rights reserved.")
      )
      (libsource (lib "eagle-import") (part "DMC4047LSD-13SO8_DIO"))
    )
    (comp (ref "CAC1.1")
      (value "C-US0402")
      (footprint "eagle-import:0402")
      (libsource (lib "eagle-import") (part "esbd-passives_vf.aVnswyxgQrGgV-hLEV-kMQ_C-US0402"))
    )
    (comp (ref "CAC2.1")
      (value "C-US0402")
      (footprint "eagle-import:0402")
      (libsource (lib "eagle-import") (part "esbd-passives_vf.aVnswyxgQrGgV-hLEV-kMQ_C-US0402"))
    )
    (comp (ref "CADC.1")
      (value "C-US0402")
      (footprint "eagle-import:0402")
      (libsource (lib "eagle-import") (part "C-US0402"))
    )
    (comp (ref "CDECAP0.1")
      (value "C-US0402")
      (footprint "eagle-import:0402")
      (libsource (lib "eagle-import") (part "C-US0402"))
    )
    (comp (ref "CDECAP1.1")
      (value "C-US0402")
      (footprint "eagle-import:0402")
      (libsource (lib "eagle-import") (part "C-US0402"))
    )
    (comp (ref "CDECAP2.1")
      (value "C-US0402")
      (footprint "eagle-import:0402")
      (libsource (lib "eagle-import") (part "C-US0402"))
    )
    (comp (ref "CDECAP3.1")
      (value "C-US0402")
      (footprint "eagle-import:0402")
      (libsource (lib "eagle-import") (part "C-US0402"))
    )
    (comp (ref "CDECAP4.1")
      (value "C-US0402")
      (footprint "eagle-import:0402")
      (libsource (lib "eagle-import") (part "C-US0402"))
    )
    (comp (ref "CDECAP5.1")
      (value "C-US0402")
      (footprint "eagle-import:0402")
      (libsource (lib "eagle-import") (part "C-US0402"))
    )
    (comp (ref "CDECAP6.1")
      (value "C-US0402")
      (footprint "eagle-import:0402")
      (libsource (lib "eagle-import") (part "C-US0402"))
    )
    (comp (ref "CDECAP7.1")
      (value "C-US0402")
      (footprint "eagle-import:0402")
      (libsource (lib "eagle-import") (part "C-US0402"))
    )
    (comp (ref "CDECAP7.3")
      (value "C-US0402")
      (footprint "eagle-import:0402")
      (libsource (lib "eagle-import") (part "C-US0402"))
    )
    (comp (ref "CDECAP8.1")
      (value "C-US0402")
      (footprint "eagle-import:0402")
      (libsource (lib "eagle-import") (part "C-US0402"))
    )
    (comp (ref "CDECAP9.1")
      (value "C-US0402")
      (footprint "eagle-import:0402")
      (libsource (lib "eagle-import") (part "C-US0402"))
    )
    (comp (ref "CH1.1")
      (value "C-US0402")
      (footprint "eagle-import:0402")
      (libsource (lib "eagle-import") (part "esbd-passives_vf.aVnswyxgQrGgV-hLEV-kMQ_C-US0402"))
    )
    (comp (ref "CH2.1")
      (value "C-US0402")
      (footprint "eagle-import:0402")
      (libsource (lib "eagle-import") (part "esbd-passives_vf.aVnswyxgQrGgV-hLEV-kMQ_C-US0402"))
    )
    (comp (ref "CH3.1")
      (value "C-US0402")
      (footprint "eagle-import:0402")
      (libsource (lib "eagle-import") (part "esbd-passives_vf.aVnswyxgQrGgV-hLEV-kMQ_C-US0402"))
    )
    (comp (ref "CH4.1")
      (value "C-US0402")
      (footprint "eagle-import:0402")
      (libsource (lib "eagle-import") (part "esbd-passives_vf.aVnswyxgQrGgV-hLEV-kMQ_C-US0402"))
    )
    (comp (ref "CL1.1")
      (value "C-US0402")
      (footprint "eagle-import:0402")
      (libsource (lib "eagle-import") (part "esbd-passives_vf.aVnswyxgQrGgV-hLEV-kMQ_C-US0402"))
    )
    (comp (ref "CL2.1")
      (value "C-US0402")
      (footprint "eagle-import:0402")
      (libsource (lib "eagle-import") (part "esbd-passives_vf.aVnswyxgQrGgV-hLEV-kMQ_C-US0402"))
    )
    (comp (ref "CL3.1")
      (value "C-US0402")
      (footprint "eagle-import:0402")
      (libsource (lib "eagle-import") (part "esbd-passives_vf.aVnswyxgQrGgV-hLEV-kMQ_C-US0402"))
    )
    (comp (ref "CL4.1")
      (value "C-US0402")
      (footprint "eagle-import:0402")
      (libsource (lib "eagle-import") (part "esbd-passives_vf.aVnswyxgQrGgV-hLEV-kMQ_C-US0402"))
    )
    (comp (ref "CRFI.1")
      (value "C-US0402")
      (footprint "eagle-import:0402")
      (libsource (lib "eagle-import") (part "esbd-passives_vf.aVnswyxgQrGgV-hLEV-kMQ_C-US0402"))
    )
    (comp (ref "DAC.1")
      (value "DAC081S101CIMKX/NOPBMK06A")
      (footprint "eagle-import:MK06A")
      (fields
        (field (name "MANUFACTURER_PART_NUMBER") "DAC081S101CIMKX/NOPB")
        (field (name "COPYRIGHT") "Copyright (C) 2024 Ultra Librarian. All rights reserved.")
      )
      (libsource (lib "eagle-import") (part "DAC081S101CIMKX/NOPBMK06A"))
    )
    (comp (ref "HPAMPS.1")
      (value "OPA2991IDRD0008A-MFG")
      (footprint "eagle-import:D0008A-MFG")
      (fields
        (field (name "MANUFACTURER_PART_NUMBER") "OPA2991IDR")
        (field (name "COPYRIGHT") "Copyright (C) 2024 Ultra Librarian. All rights reserved.")
      )
      (libsource (lib "eagle-import") (part "OPA2991IDRD0008A-MFG"))
    )
    (comp (ref "OUTBUFFER.1")
      (value "OPA552UA/2K5D8")
      (footprint "eagle-import:D8")
      (fields
        (field (name "MANUFACTURER_PART_NUMBER") "OPA552UA/2K5")
        (field (name "COPYRIGHT") "Copyright (C) 2024 Ultra Librarian. All rights reserved.")
      )
      (libsource (lib "eagle-import") (part "OPA552UA/2K5D8"))
    )
    (comp (ref "PGA.1")
      (value "LTC6911CMS-1TRPBFMSOP-10_MS_LIT")
      (footprint "eagle-import:MSOP-10_MS_LIT")
      (fields
        (field (name "MANUFACTURER_PART_NUMBER") "LTC6911CMS-1#TRPBF")
        (field (name "COPYRIGHT") "Copyright (C) 2024 Ultra Librarian. All rights reserved.")
      )
      (libsource (lib "eagle-import") (part "LTC6911CMS-1TRPBFMSOP-10_MS_LIT"))
    )
    (comp (ref "PREAMPLIFIER.1")
      (value "INA818IDSOIC-8_TEX")
      (footprint "eagle-import:SOIC-8_TEX")
      (fields
        (field (name "MANUFACTURER_PART_NUMBER") "INA818ID")
        (field (name "COPYRIGHT") "Copyright (C) 2024 Ultra Librarian. All rights reserved.")
      )
      (libsource (lib "eagle-import") (part "INA818IDSOIC-8_TEX"))
    )
    (comp (ref "RAC1.1")
      (value "R-US0402")
      (footprint "eagle-import:0402")
      (libsource (lib "eagle-import") (part "esbd-passives_vf.aVnswyxgQrGgV-hLEV-kMQ_R-US0402"))
    )
    (comp (ref "RAC2.1")
      (value "R-US0402")
      (footprint "eagle-import:0402")
      (libsource (lib "eagle-import") (part "esbd-passives_vf.aVnswyxgQrGgV-hLEV-kMQ_R-US0402"))
    )
    (comp (ref "RAC3.1")
      (value "R-US0402")
      (footprint "eagle-import:0402")
      (libsource (lib "eagle-import") (part "esbd-passives_vf.aVnswyxgQrGgV-hLEV-kMQ_R-US0402"))
    )
    (comp (ref "RADC.1")
      (value "R-US0402")
      (footprint "eagle-import:0402")
      (libsource (lib "eagle-import") (part "esbd-passives_vf.aVnswyxgQrGgV-hLEV-kMQ_R-US0402"))
    )
    (comp (ref "RBOOT0.1")
      (value "R-US0603")
      (footprint "eagle-import:0603")
      (libsource (lib "eagle-import") (part "esbd-passives_vf.aVnswyxgQrGgV-hLEV-kMQ_R-US0603"))
    )
    (comp (ref "RBOOT1.1")
      (value "R-US0603")
      (footprint "eagle-import:0603")
      (libsource (lib "eagle-import") (part "esbd-passives_vf.aVnswyxgQrGgV-hLEV-kMQ_R-US0603"))
    )
    (comp (ref "RBOOT2.1")
      (value "R-US0603")
      (footprint "eagle-import:0603")
      (libsource (lib "eagle-import") (part "esbd-passives_vf.aVnswyxgQrGgV-hLEV-kMQ_R-US0603"))
    )
    (comp (ref "RBOOT3.1")
      (value "R-US0603")
      (footprint "eagle-import:0603")
      (libsource (lib "eagle-import") (part "esbd-passives_vf.aVnswyxgQrGgV-hLEV-kMQ_R-US0603"))
    )
    (comp (ref "RBYPASSVDD.1")
      (value "R-US0402")
      (footprint "eagle-import:0402")
      (libsource (lib "eagle-import") (part "esbd-passives_vf.aVnswyxgQrGgV-hLEV-kMQ_R-US0402"))
    )
    (comp (ref "RBYPASSVSS.1")
      (value "R-US0402")
      (footprint "eagle-import:0402")
      (libsource (lib "eagle-import") (part "esbd-passives_vf.aVnswyxgQrGgV-hLEV-kMQ_R-US0402"))
    )
    (comp (ref "RDAC.1")
      (value "R-US0402")
      (footprint "eagle-import:0402")
      (libsource (lib "eagle-import") (part "esbd-passives_vf.aVnswyxgQrGgV-hLEV-kMQ_R-US0402"))
    )
    (comp (ref "RGAINPREAMP.1")
      (value "R-US0402")
      (footprint "eagle-import:0402")
      (libsource (lib "eagle-import") (part "esbd-passives_vf.aVnswyxgQrGgV-hLEV-kMQ_R-US0402"))
    )
    (comp (ref "RH1.1")
      (value "R-US0402")
      (footprint "eagle-import:0402")
      (libsource (lib "eagle-import") (part "esbd-passives_vf.aVnswyxgQrGgV-hLEV-kMQ_R-US0402"))
    )
    (comp (ref "RH2.1")
      (value "R-US0402")
      (footprint "eagle-import:0402")
      (libsource (lib "eagle-import") (part "esbd-passives_vf.aVnswyxgQrGgV-hLEV-kMQ_R-US0402"))
    )
    (comp (ref "RH3.1")
      (value "R-US0402")
      (footprint "eagle-import:0402")
      (libsource (lib "eagle-import") (part "esbd-passives_vf.aVnswyxgQrGgV-hLEV-kMQ_R-US0402"))
    )
    (comp (ref "RH4.1")
      (value "R-US0402")
      (footprint "eagle-import:0402")
      (libsource (lib "eagle-import") (part "esbd-passives_vf.aVnswyxgQrGgV-hLEV-kMQ_R-US0402"))
    )
    (comp (ref "RHP0.1")
      (value "R-US0603")
      (footprint "eagle-import:0603")
      (libsource (lib "eagle-import") (part "esbd-passives_vf.aVnswyxgQrGgV-hLEV-kMQ_R-US0603"))
    )
    (comp (ref "RHP1.1")
      (value "R-US0603")
      (footprint "eagle-import:0603")
      (libsource (lib "eagle-import") (part "esbd-passives_vf.aVnswyxgQrGgV-hLEV-kMQ_R-US0603"))
    )
    (comp (ref "RHP2.1")
      (value "R-US0603")
      (footprint "eagle-import:0603")
      (libsource (lib "eagle-import") (part "esbd-passives_vf.aVnswyxgQrGgV-hLEV-kMQ_R-US0603"))
    )
    (comp (ref "RHP3.1")
      (value "R-US0603")
      (footprint "eagle-import:0603")
      (libsource (lib "eagle-import") (part "esbd-passives_vf.aVnswyxgQrGgV-hLEV-kMQ_R-US0603"))
    )
    (comp (ref "RL1.1")
      (value "R-US0402")
      (footprint "eagle-import:0402")
      (libsource (lib "eagle-import") (part "esbd-passives_vf.aVnswyxgQrGgV-hLEV-kMQ_R-US0402"))
    )
    (comp (ref "RL2.1")
      (value "R-US0402")
      (footprint "eagle-import:0402")
      (libsource (lib "eagle-import") (part "esbd-passives_vf.aVnswyxgQrGgV-hLEV-kMQ_R-US0402"))
    )
    (comp (ref "RL3.1")
      (value "R-US0402")
      (footprint "eagle-import:0402")
      (libsource (lib "eagle-import") (part "esbd-passives_vf.aVnswyxgQrGgV-hLEV-kMQ_R-US0402"))
    )
    (comp (ref "RL4.1")
      (value "R-US0402")
      (footprint "eagle-import:0402")
      (libsource (lib "eagle-import") (part "esbd-passives_vf.aVnswyxgQrGgV-hLEV-kMQ_R-US0402"))
    )
    (comp (ref "RSTIM.1")
      (value "R-US0603")
      (footprint "eagle-import:0603")
      (libsource (lib "eagle-import") (part "esbd-passives_vf.aVnswyxgQrGgV-hLEV-kMQ_R-US0603"))
    )
    (comp (ref "AMPREF.0")
      (value "OPA552UA/2K5D8")
      (footprint "eagle-import:D8")
      (fields
        (field (name "MANUFACTURER_PART_NUMBER") "OPA552UA/2K5")
        (field (name "COPYRIGHT") "Copyright (C) 2024 Ultra Librarian. All rights reserved.")
      )
      (libsource (lib "eagle-import") (part "OPA552UA/2K5D8"))
    )
    (comp (ref "AMPREF.1")
      (value "OPA552UA/2K5D8")
      (footprint "eagle-import:D8")
      (fields
        (field (name "MANUFACTURER_PART_NUMBER") "OPA552UA/2K5")
        (field (name "COPYRIGHT") "Copyright (C) 2024 Ultra Librarian. All rights reserved.")
      )
      (libsource (lib "eagle-import") (part "OPA552UA/2K5D8"))
    )
    (comp (ref "BOOSTCTRL")
      (value "LM51581QRTERQ1RTE0016K-MFG")
      (footprint "eagle-import:RTE0016K-MFG")
      (fields
        (field (name "MANUFACTURER_PART_NUMBER") "LM51581QRTERQ1")
        (field (name "COPYRIGHT") "Copyright (C) 2024 Ultra Librarian. All rights reserved.")
      )
      (libsource (lib "eagle-import") (part "LM51581QRTERQ1RTE0016K-MFG"))
    )
    (comp (ref "BOOSTFBPOT")
      (value "3362P-1-103LFPOT_3362P")
      (footprint "eagle-import:POT_3362P")
      (fields
        (field (name "MANUFACTURER_PART_NUMBER") "3362P-1-103LF")
        (field (name "COPYRIGHT") "Copyright (C) 2024 Ultra Librarian. All rights reserved.")
      )
      (libsource (lib "eagle-import") (part "3362P-1-103LFPOT_3362P"))
    )
    (comp (ref "CBIAS")
      (value "1uF")
      (footprint "eagle-import:0805")
      (libsource (lib "eagle-import") (part "C-US0805"))
    )
    (comp (ref "CCOMP")
      (value "47n")
      (footprint "eagle-import:0603")
      (libsource (lib "eagle-import") (part "C-US0603"))
    )
    (comp (ref "CCOMP1")
      (value "390p")
      (footprint "eagle-import:0603")
      (libsource (lib "eagle-import") (part "C-US0603"))
    )
    (comp (ref "CDECAPREF.0")
      (value "C-US0402")
      (footprint "eagle-import:0402")
      (libsource (lib "eagle-import") (part "C-US0402"))
    )
    (comp (ref "CDECAPREF.1")
      (value "C-US0402")
      (footprint "eagle-import:0402")
      (libsource (lib "eagle-import") (part "C-US0402"))
    )
    (comp (ref "COUT1")
      (value "1uF")
      (footprint "eagle-import:0805")
      (libsource (lib "eagle-import") (part "C-US0805"))
    )
    (comp (ref "COUT2")
      (value "100nF")
      (footprint "eagle-import:0805")
      (libsource (lib "eagle-import") (part "C-US0805"))
    )
    (comp (ref "COUT3")
      (value "100nF")
      (footprint "eagle-import:0805")
      (libsource (lib "eagle-import") (part "C-US0805"))
    )
    (comp (ref "CREF0.0")
      (value "C-US0603")
      (footprint "eagle-import:0603")
      (libsource (lib "eagle-import") (part "C-US0603"))
    )
    (comp (ref "CREF0.1")
      (value "C-US0603")
      (footprint "eagle-import:0603")
      (libsource (lib "eagle-import") (part "C-US0603"))
    )
    (comp (ref "CREF1.0")
      (value "C-US0805")
      (footprint "eagle-import:0805")
      (libsource (lib "eagle-import") (part "C-US0805"))
    )
    (comp (ref "CREF1.1")
      (value "C-US0805")
      (footprint "eagle-import:0805")
      (libsource (lib "eagle-import") (part "C-US0805"))
    )
    (comp (ref "CREF2.0")
      (value "C-US0603")
      (footprint "eagle-import:0603")
      (libsource (lib "eagle-import") (part "C-US0603"))
    )
    (comp (ref "CREF2.1")
      (value "C-US0603")
      (footprint "eagle-import:0603")
      (libsource (lib "eagle-import") (part "C-US0603"))
    )
    (comp (ref "CREF3.0")
      (value "C-US0805")
      (footprint "eagle-import:0805")
      (libsource (lib "eagle-import") (part "C-US0805"))
    )
    (comp (ref "CREF3.1")
      (value "C-US0805")
      (footprint "eagle-import:0805")
      (libsource (lib "eagle-import") (part "C-US0805"))
    )
    (comp (ref "CSS")
      (value "12n")
      (footprint "eagle-import:0603")
      (libsource (lib "eagle-import") (part "C-US0603"))
    )
    (comp (ref "CVDD")
      (value "10uF")
      (footprint "eagle-import:0805")
      (libsource (lib "eagle-import") (part "C-US0805"))
    )
    (comp (ref "D1")
      (value "B160-13-FSMA_DIO")
      (footprint "eagle-import:SMA_DIO")
      (fields
        (field (name "MANUFACTURER_PART_NUMBER") "B160-13-F")
        (field (name "COPYRIGHT") "Copyright (C) 2024 Ultra Librarian. All rights reserved.")
      )
      (libsource (lib "eagle-import") (part "B160-13-FSMA_DIO"))
    )
    (comp (ref "J3")
      (value "MA03-1_TH_2.54MM")
      (footprint "eagle-import:MA03-1_TH_2.54MM")
      (libsource (lib "eagle-import") (part "MA03-1_TH_2.54MM"))
    )
    (comp (ref "J4")
      (value "MA03-1_TH_2.54MM")
      (footprint "eagle-import:MA03-1_TH_2.54MM")
      (libsource (lib "eagle-import") (part "MA03-1_TH_2.54MM"))
    )
    (comp (ref "NAREFH.0")
      (value "R-US0402")
      (footprint "eagle-import:0402")
      (libsource (lib "eagle-import") (part "R-US0402"))
    )
    (comp (ref "NAREFH.1")
      (value "R-US0402")
      (footprint "eagle-import:0402")
      (libsource (lib "eagle-import") (part "R-US0402"))
    )
    (comp (ref "NAREFL.0")
      (value "R-US0402")
      (footprint "eagle-import:0402")
      (libsource (lib "eagle-import") (part "R-US0402"))
    )
    (comp (ref "NAREFL.1\\")
      (value "R-US0402")
      (footprint "eagle-import:0402")
      (libsource (lib "eagle-import") (part "R-US0402"))
    )
    (comp (ref "RBOOSTFB0")
      (value "2.5k")
      (footprint "eagle-import:0603")
      (libsource (lib "eagle-import") (part "esbd-passives_vf.aVnswyxgQrGgV-hLEV-kMQ_R-US0603"))
    )
    (comp (ref "RBOOSTFB1")
      (value "100k")
      (footprint "eagle-import:0603")
      (libsource (lib "eagle-import") (part "esbd-passives_vf.aVnswyxgQrGgV-hLEV-kMQ_R-US0603"))
    )
    (comp (ref "RBOOSTMID0.0")
      (value "22k")
      (footprint "eagle-import:0603")
      (libsource (lib "eagle-import") (part "esbd-passives_vf.aVnswyxgQrGgV-hLEV-kMQ_R-US0603"))
    )
    (comp (ref "RBOOSTMID0.1")
      (value "22k")
      (footprint "eagle-import:0603")
      (libsource (lib "eagle-import") (part "esbd-passives_vf.aVnswyxgQrGgV-hLEV-kMQ_R-US0603"))
    )
    (comp (ref "RBOOSTMID1.0")
      (value "22k")
      (footprint "eagle-import:0603")
      (libsource (lib "eagle-import") (part "esbd-passives_vf.aVnswyxgQrGgV-hLEV-kMQ_R-US0603"))
    )
    (comp (ref "RBOOSTMID1.1")
      (value "22k")
      (footprint "eagle-import:0603")
      (libsource (lib "eagle-import") (part "esbd-passives_vf.aVnswyxgQrGgV-hLEV-kMQ_R-US0603"))
    )
    (comp (ref "RCOMP")
      (value "1.47k")
      (footprint "eagle-import:0603")
      (libsource (lib "eagle-import") (part "R-US0603"))
    )
    (comp (ref "RT")
      (value "26.7k")
      (footprint "eagle-import:0603")
      (libsource (lib "eagle-import") (part "R-US0603"))
    )
    (comp (ref "U$1")
      (value "MSS1246-COILCRAFT")
      (footprint "eagle-import:MSS1246-COILCRAFT")
      (libsource (lib "eagle-import") (part "MSS1246-COILCRAFT"))
    )
    (comp (ref "U1")
      (value "BUF634AIDR")
      (footprint "eagle-import:SOIC127P599X175-8N")
      (libsource (lib "eagle-import") (part "BUF634AIDR"))
    )
    (comp (ref "U2")
      (value "BUF634AIDR")
      (footprint "eagle-import:SOIC127P599X175-8N")
      (libsource (lib "eagle-import") (part "BUF634AIDR"))
    )
  )
  (nets
    (net (code "1") (name "BANDPASSOUT1.0") (class "Default")
      (node (ref "BANDPASSFILTER1.0") (pin "6") (pinfunction "IN_B-_6") (pintype "passive"))
      (node (ref "BANDPASSFILTER1.0") (pin "7") (pinfunction "OUT_B_7") (pintype "output"))
      (node (ref "CL1.0") (pin "1") (pinfunction "1_1") (pintype "passive"))
      (node (ref "PGA.0") (pin "1") (pinfunction "INA_1") (pintype "input"))
    )
    (net (code "2") (name "BANDPASSOUT1.1") (class "Default")
      (node (ref "BANDPASSFILTER1.1") (pin "6") (pinfunction "IN_B-_6") (pintype "passive"))
      (node (ref "BANDPASSFILTER1.1") (pin "7") (pinfunction "OUT_B_7") (pintype "output"))
      (node (ref "CL1.1") (pin "2") (pinfunction "2_2") (pintype "passive"))
      (node (ref "PGA.1") (pin "1") (pinfunction "INA_1") (pintype "input"))
    )
    (net (code "3") (name "BANDPASSOUT2.0") (class "Default")
      (node (ref "BANDPASSFILTER2.0") (pin "6") (pinfunction "IN_B-_6") (pintype "passive"))
      (node (ref "BANDPASSFILTER2.0") (pin "7") (pinfunction "OUT_B_7") (pintype "output"))
      (node (ref "CL3.0") (pin "1") (pinfunction "1_1") (pintype "passive"))
      (node (ref "PGA.0") (pin "3") (pinfunction "INB_3") (pintype "input"))
    )
    (net (code "4") (name "BANDPASSOUT2.1") (class "Default")
      (node (ref "BANDPASSFILTER2.1") (pin "6") (pinfunction "IN_B-_6") (pintype "passive"))
      (node (ref "BANDPASSFILTER2.1") (pin "7") (pinfunction "OUT_B_7") (pintype "output"))
      (node (ref "CL3.1") (pin "2") (pinfunction "2_2") (pintype "passive"))
      (node (ref "PGA.1") (pin "3") (pinfunction "INB_3") (pintype "input"))
    )
    (net (code "5") (name "BOOSTCTLCOMP") (class "Default")
      (node (ref "BOOSTCTRL") (pin "8") (pinfunction "COMP_8") (pintype "passive"))
      (node (ref "CCOMP1") (pin "1") (pinfunction "1_1") (pintype "passive"))
      (node (ref "RCOMP") (pin "1") (pinfunction "1_1") (pintype "passive"))
    )
    (net (code "6") (name "BOOSTCTLCOMP2") (class "Default")
      (node (ref "CCOMP") (pin "1") (pinfunction "1_1") (pintype "passive"))
      (node (ref "RCOMP") (pin "2") (pinfunction "2_2") (pintype "passive"))
    )
    (net (code "7") (name "BOOSTCTLOUT") (class "Default")
      (node (ref "BOOSTCTRL") (pin "13") (pinfunction "SW_2_13") (pintype "passive"))
      (node (ref "BOOSTCTRL") (pin "14") (pinfunction "SW_14") (pintype "passive"))
      (node (ref "D1") (pin "2") (pinfunction "2_2") (pintype "passive"))
      (node (ref "U$1") (pin "P$2") (pinfunction "P$2_P$2") (pintype "bidirectional"))
    )
    (net (code "8") (name "BOOSTCTLRT") (class "Default")
      (node (ref "BOOSTCTRL") (pin "5") (pinfunction "RT_5") (pintype "passive"))
      (node (ref "RT") (pin "1") (pinfunction "1_1") (pintype "passive"))
    )
    (net (code "9") (name "BOOSTCTLSS") (class "Default")
      (node (ref "BOOSTCTRL") (pin "10") (pinfunction "SS_10") (pintype "passive"))
      (node (ref "CSS") (pin "1") (pinfunction "1_1") (pintype "passive"))
    )
    (net (code "10") (name "BOOSTFB") (class "Default")
      (node (ref "BOOSTCTRL") (pin "9") (pinfunction "FB_9") (pintype "passive"))
      (node (ref "BOOSTFBPOT") (pin "2") (pinfunction "2_2") (pintype "passive"))
      (node (ref "RBOOSTFB1") (pin "1") (pinfunction "1_1") (pintype "passive"))
    )
    (net (code "11") (name "BOOTNG.0") (class "Default")
      (node (ref "BOOTSTRAP.0") (pin "2") (pinfunction "NG2_2") (pintype "passive"))
      (node (ref "RBOOT2.0") (pin "2") (pinfunction "2_2") (pintype "passive"))
      (node (ref "RBOOT3.0") (pin "1") (pinfunction "1_1") (pintype "passive"))
    )
    (net (code "12") (name "BOOTNG.1") (class "Default")
      (node (ref "BOOTSTRAPPER.1") (pin "2") (pinfunction "NG2_2") (pintype "passive"))
      (node (ref "RBOOT2.1") (pin "2") (pinfunction "2_2") (pintype "passive"))
      (node (ref "RBOOT3.1") (pin "1") (pinfunction "1_1") (pintype "passive"))
    )
    (net (code "13") (name "BOOTPG.0") (class "Default")
      (node (ref "BOOTSTRAP.0") (pin "4") (pinfunction "PG1_4") (pintype "passive"))
      (node (ref "RBOOT0.0") (pin "2") (pinfunction "2_2") (pintype "passive"))
      (node (ref "RBOOT1.0") (pin "1") (pinfunction "1_1") (pintype "passive"))
    )
    (net (code "14") (name "BOOTPG.1") (class "Default")
      (node (ref "BOOTSTRAPPER.1") (pin "4") (pinfunction "PG1_4") (pintype "passive"))
      (node (ref "RBOOT0.1") (pin "2") (pinfunction "2_2") (pintype "passive"))
      (node (ref "RBOOT1.1") (pin "1") (pinfunction "1_1") (pintype "passive"))
    )
    (net (code "15") (name "CH1") (class "Default")
      (node (ref "J1") (pin "1") (pinfunction "1_1") (pintype "passive"))
      (node (ref "U4") (pin "1") (pinfunction "D_1") (pintype "passive"))
    )
    (net (code "16") (name "CH2") (class "Default")
      (node (ref "J1") (pin "3") (pinfunction "3_3") (pintype "passive"))
      (node (ref "U5") (pin "1") (pinfunction "D_1") (pintype "passive"))
    )
    (net (code "17") (name "CH3") (class "Default")
      (node (ref "J1") (pin "5") (pinfunction "5_5") (pintype "passive"))
      (node (ref "U6") (pin "1") (pinfunction "D_1") (pintype "passive"))
    )
    (net (code "18") (name "CH4") (class "Default")
      (node (ref "J1") (pin "7") (pinfunction "7_7") (pintype "passive"))
      (node (ref "U7") (pin "1") (pinfunction "D_1") (pintype "passive"))
    )
    (net (code "19") (name "CH5") (class "Default")
      (node (ref "J2") (pin "1") (pinfunction "1_1") (pintype "passive"))
      (node (ref "U8") (pin "1") (pinfunction "D_1") (pintype "passive"))
    )
    (net (code "20") (name "CH6") (class "Default")
      (node (ref "J2") (pin "3") (pinfunction "3_3") (pintype "passive"))
      (node (ref "U10") (pin "1") (pinfunction "D_1") (pintype "passive"))
    )
    (net (code "21") (name "CH7") (class "Default")
      (node (ref "J2") (pin "5") (pinfunction "5_5") (pintype "passive"))
      (node (ref "U11") (pin "1") (pinfunction "D_1") (pintype "passive"))
    )
    (net (code "22") (name "CH8") (class "Default")
      (node (ref "J2") (pin "7") (pinfunction "7_7") (pintype "passive"))
      (node (ref "U12") (pin "1") (pinfunction "D_1") (pintype "passive"))
    )
    (net (code "23") (name "DIG_CSN_ADC.0") (class "Default")
      (node (ref "ADC.0") (pin "4") (pinfunction "CS_N_4") (pintype "input"))
      (node (ref "RADC.3") (pin "1") (pinfunction "1_1") (pintype "passive"))
      (node (ref "U$2") (pin "18") (pinfunction "V8_18") (pintype "bidirectional"))
    )
    (net (code "24") (name "DIG_CSN_ADC.1") (class "Default")
      (node (ref "ADC.1") (pin "4") (pinfunction "CS_N_4") (pintype "input"))
      (node (ref "RADC.1") (pin "1") (pinfunction "1_1") (pintype "passive"))
      (node (ref "U$2") (pin "99") (pinfunction "N4_99") (pintype "bidirectional"))
    )
    (net (code "25") (name "DIG_CSN_HP_DAC.0") (class "Default")
      (node (ref "DAC.0") (pin "6") (pinfunction "~{SYNC}_6") (pintype "input"))
      (node (ref "RDAC.2") (pin "2") (pinfunction "2_2") (pintype "passive"))
      (node (ref "U$2") (pin "16") (pinfunction "V9_16") (pintype "bidirectional"))
    )
    (net (code "26") (name "DIG_CSN_HP_DAC.1") (class "Default")
      (node (ref "DAC.1") (pin "6") (pinfunction "~{SYNC}_6") (pintype "input"))
      (node (ref "RDAC.1") (pin "2") (pinfunction "2_2") (pintype "passive"))
      (node (ref "U$2") (pin "101") (pinfunction "N3_101") (pintype "bidirectional"))
    )
    (net (code "27") (name "DIG_ENABLECH1.0") (class "Default")
      (node (ref "RCH1.0") (pin "1") (pinfunction "1_1") (pintype "passive"))
      (node (ref "U$2") (pin "77") (pinfunction "V4_77") (pintype "bidirectional"))
      (node (ref "U4") (pin "5") (pinfunction "EN_5") (pintype "passive"))
    )
    (net (code "28") (name "DIG_ENABLECH1.1") (class "Default")
      (node (ref "RCH5.0") (pin "1") (pinfunction "1_1") (pintype "passive"))
      (node (ref "U$2") (pin "157") (pinfunction "H4_157") (pintype "bidirectional"))
      (node (ref "U8") (pin "5") (pinfunction "EN_5") (pintype "passive"))
    )
    (net (code "29") (name "DIG_ENABLECH2.0") (class "Default")
      (node (ref "RCH2.0") (pin "1") (pinfunction "1_1") (pintype "passive"))
      (node (ref "U$2") (pin "63") (pinfunction "AA1_63") (pintype "bidirectional"))
      (node (ref "U5") (pin "5") (pinfunction "EN_5") (pintype "passive"))
    )
    (net (code "30") (name "DIG_ENABLECH2.1") (class "Default")
      (node (ref "RCH6.0") (pin "1") (pinfunction "1_1") (pintype "passive"))
      (node (ref "U$2") (pin "154") (pinfunction "Y14_154") (pintype "bidirectional"))
      (node (ref "U10") (pin "5") (pinfunction "EN_5") (pintype "passive"))
    )
    (net (code "31") (name "DIG_ENABLECH3.0") (class "Default")
      (node (ref "RCH3.0") (pin "1") (pinfunction "1_1") (pintype "passive"))
      (node (ref "U$2") (pin "73") (pinfunction "AB15_73") (pintype "bidirectional"))
      (node (ref "U6") (pin "5") (pinfunction "EN_5") (pintype "passive"))
    )
    (net (code "32") (name "DIG_ENABLECH3.1") (class "Default")
      (node (ref "RCH7.0") (pin "1") (pinfunction "1_1") (pintype "passive"))
      (node (ref "U$2") (pin "155") (pinfunction "Y11_155") (pintype "bidirectional"))
      (node (ref "U11") (pin "5") (pinfunction "EN_5") (pintype "passive"))
    )
    (net (code "33") (name "DIG_ENABLECH4.0") (class "Default")
      (node (ref "RCH.40") (pin "1") (pinfunction "1_1") (pintype "passive"))
      (node (ref "U$2") (pin "61") (pinfunction "U1_61") (pintype "bidirectional"))
      (node (ref "U7") (pin "5") (pinfunction "EN_5") (pintype "passive"))
    )
    (net (code "34") (name "DIG_ENABLECH4.1") (class "Default")
      (node (ref "RCH8.0") (pin "1") (pinfunction "1_1") (pintype "passive"))
      (node (ref "U$2") (pin "152") (pinfunction "W14_152") (pintype "bidirectional"))
      (node (ref "U12") (pin "5") (pinfunction "EN_5") (pintype "passive"))
    )
    (net (code "35") (name "DIG_PGAGAIN0.0") (class "Default")
      (node (ref "PGA.0") (pin "4") (pinfunction "G0_4") (pintype "input"))
      (node (ref "U$2") (pin "30") (pinfunction "W5_30") (pintype "bidirectional"))
    )
    (net (code "36") (name "DIG_PGAGAIN0.1") (class "Default")
      (node (ref "PGA.1") (pin "4") (pinfunction "G0_4") (pintype "input"))
      (node (ref "U$2") (pin "107") (pinfunction "M6_107") (pintype "bidirectional"))
    )
    (net (code "37") (name "DIG_PGAGAIN1.0") (class "Default")
      (node (ref "PGA.0") (pin "5") (pinfunction "G1_5") (pintype "input"))
      (node (ref "U$2") (pin "28") (pinfunction "W6_28") (pintype "bidirectional"))
    )
    (net (code "38") (name "DIG_PGAGAIN1.1") (class "Default")
      (node (ref "PGA.1") (pin "5") (pinfunction "G1_5") (pintype "input"))
      (node (ref "U$2") (pin "109") (pinfunction "M5_109") (pintype "bidirectional"))
    )
    (net (code "39") (name "DIG_PGAGAIN2.0") (class "Default")
      (node (ref "PGA.0") (pin "6") (pinfunction "G2_6") (pintype "input"))
      (node (ref "U$2") (pin "26") (pinfunction "Y7_26") (pintype "bidirectional"))
    )
    (net (code "40") (name "DIG_PGAGAIN2.1") (class "Default")
      (node (ref "PGA.1") (pin "6") (pinfunction "G2_6") (pintype "input"))
      (node (ref "U$2") (pin "105") (pinfunction "L4_105") (pintype "bidirectional"))
    )
    (net (code "41") (name "DIG_SCLK.0") (class "Default")
      (node (ref "ADC.0") (pin "2") (pinfunction "SCLK_2") (pintype "input"))
      (node (ref "DAC.0") (pin "5") (pinfunction "SCLK_5") (pintype "input"))
      (node (ref "U$2") (pin "22") (pinfunction "W7_22") (pintype "bidirectional"))
    )
    (net (code "42") (name "DIG_SCLK.1") (class "Default")
      (node (ref "ADC.1") (pin "2") (pinfunction "SCLK_2") (pintype "input"))
      (node (ref "DAC.1") (pin "5") (pinfunction "SCLK_5") (pintype "input"))
      (node (ref "U$2") (pin "95") (pinfunction "P5_95") (pintype "bidirectional"))
    )
    (net (code "43") (name "DIG_SDA.0") (class "Default")
      (node (ref "ADC.0") (pin "3") (pinfunction "SDO_3") (pintype "output"))
      (node (ref "DAC.0") (pin "4") (pinfunction "DIN_4") (pintype "input"))
      (node (ref "U$2") (pin "20") (pinfunction "V7_20") (pintype "bidirectional"))
    )
    (net (code "44") (name "DIG_SDA.1") (class "Default")
      (node (ref "ADC.1") (pin "3") (pinfunction "SDO_3") (pintype "output"))
      (node (ref "DAC.1") (pin "4") (pinfunction "DIN_4") (pintype "input"))
      (node (ref "U$2") (pin "97") (pinfunction "P4_97") (pintype "bidirectional"))
    )
    (net (code "45") (name "DIG_SELECTCH1.0") (class "Default")
      (node (ref "U$2") (pin "79") (pinfunction "W4_79") (pintype "bidirectional"))
      (node (ref "U4") (pin "6") (pinfunction "SEL_6") (pintype "passive"))
    )
    (net (code "46") (name "DIG_SELECTCH1.1") (class "Default")
      (node (ref "U$2") (pin "159") (pinfunction "G4_159") (pintype "bidirectional"))
      (node (ref "U8") (pin "6") (pinfunction "SEL_6") (pintype "passive"))
    )
    (net (code "47") (name "DIG_SELECTCH2.0") (class "Default")
      (node (ref "U$2") (pin "65") (pinfunction "AB1_65") (pintype "bidirectional"))
      (node (ref "U5") (pin "6") (pinfunction "SEL_6") (pintype "passive"))
    )
    (net (code "48") (name "DIG_SELECTCH2.1") (class "Default")
      (node (ref "U$2") (pin "156") (pinfunction "Y12_156") (pintype "bidirectional"))
      (node (ref "U10") (pin "6") (pinfunction "SEL_6") (pintype "passive"))
    )
    (net (code "49") (name "DIG_SELECTCH3.0") (class "Default")
      (node (ref "U$2") (pin "71") (pinfunction "AA15_71") (pintype "bidirectional"))
      (node (ref "U6") (pin "6") (pinfunction "SEL_6") (pintype "passive"))
    )
    (net (code "50") (name "DIG_SELECTCH3.1") (class "Default")
      (node (ref "U$2") (pin "153") (pinfunction "V14_153") (pintype "bidirectional"))
      (node (ref "U11") (pin "6") (pinfunction "SEL_6") (pintype "passive"))
    )
    (net (code "51") (name "DIG_SELECTCH4.0") (class "Default")
      (node (ref "U$2") (pin "59") (pinfunction "T1_59") (pintype "bidirectional"))
      (node (ref "U7") (pin "6") (pinfunction "SEL_6") (pintype "passive"))
    )
    (net (code "52") (name "DIG_SELECTCH4.1") (class "Default")
      (node (ref "U$2") (pin "150") (pinfunction "T15_150") (pintype "bidirectional"))
      (node (ref "U12") (pin "6") (pinfunction "SEL_6") (pintype "passive"))
    )
    (net (code "53") (name "GAIN1.0") (class "Default")
      (node (ref "PREAMPLIFIER.0") (pin "8") (pinfunction "RG_8") (pintype "passive"))
      (node (ref "RGAINPREAMP.0") (pin "1") (pinfunction "1_1") (pintype "passive"))
    )
    (net (code "54") (name "GAIN1.1") (class "Default")
      (node (ref "PREAMPLIFIER.1") (pin "8") (pinfunction "RG_8") (pintype "passive"))
      (node (ref "RGAINPREAMP.1") (pin "1") (pinfunction "1_1") (pintype "passive"))
    )
    (net (code "55") (name "GAIN2.0") (class "Default")
      (node (ref "PREAMPLIFIER.0") (pin "1") (pinfunction "RG_2_1") (pintype "passive"))
      (node (ref "RGAINPREAMP.0") (pin "2") (pinfunction "2_2") (pintype "passive"))
    )
    (net (code "56") (name "GAIN2.1") (class "Default")
      (node (ref "PREAMPLIFIER.1") (pin "1") (pinfunction "RG_2_1") (pintype "passive"))
      (node (ref "RGAINPREAMP.1") (pin "2") (pinfunction "2_2") (pintype "passive"))
    )
    (net (code "57") (name "HCP_BUF.0") (class "Default")
      (node (ref "HPAMPS.0") (pin "6") (pinfunction "IN2-_6") (pintype "tri_state"))
      (node (ref "HPAMPS.0") (pin "7") (pinfunction "OUT2_7") (pintype "passive"))
      (node (ref "RHP0.0") (pin "2") (pinfunction "2_2") (pintype "passive"))
    )
    (net (code "58") (name "HCP_BUF.1") (class "Default")
      (node (ref "HPAMPS.1") (pin "6") (pinfunction "IN2-_6") (pintype "tri_state"))
      (node (ref "HPAMPS.1") (pin "7") (pinfunction "OUT2_7") (pintype "passive"))
      (node (ref "RHP3.1") (pin "1") (pinfunction "1_1") (pintype "passive"))
    )
    (net (code "59") (name "HCP_M.0") (class "Default")
      (node (ref "HPAMPS.0") (pin "2") (pinfunction "IN1-_2") (pintype "tri_state"))
      (node (ref "RHP1.0") (pin "2") (pinfunction "2_2") (pintype "passive"))
      (node (ref "RHP3.0") (pin "1") (pinfunction "1_1") (pintype "passive"))
    )
    (net (code "60") (name "HCP_M.1") (class "Default")
      (node (ref "HPAMPS.1") (pin "2") (pinfunction "IN1-_2") (pintype "tri_state"))
      (node (ref "RHP0.1") (pin "1") (pinfunction "1_1") (pintype "passive"))
      (node (ref "RHP1.1") (pin "2") (pinfunction "2_2") (pintype "passive"))
    )
    (net (code "61") (name "HCP_P.0") (class "Default")
      (node (ref "HPAMPS.0") (pin "3") (pinfunction "IN1+_3") (pintype "tri_state"))
      (node (ref "RHP0.0") (pin "1") (pinfunction "1_1") (pintype "passive"))
      (node (ref "RHP2.0") (pin "1") (pinfunction "1_1") (pintype "passive"))
    )
    (net (code "62") (name "HCP_P.1") (class "Default")
      (node (ref "HPAMPS.1") (pin "3") (pinfunction "IN1+_3") (pintype "tri_state"))
      (node (ref "RHP2.1") (pin "1") (pinfunction "1_1") (pintype "passive"))
      (node (ref "RHP3.1") (pin "2") (pinfunction "2_2") (pintype "passive"))
    )
    (net (code "63") (name "HCP_VSTIM.0") (class "Default")
      (node (ref "HPAMPS.0") (pin "1") (pinfunction "OUT1_1") (pintype "passive"))
      (node (ref "RHP3.0") (pin "2") (pinfunction "2_2") (pintype "passive"))
      (node (ref "RSTIM.0") (pin "1") (pinfunction "1_1") (pintype "passive"))
    )
    (net (code "64") (name "HCP_VSTIM.1") (class "Default")
      (node (ref "HPAMPS.1") (pin "1") (pinfunction "OUT1_1") (pintype "passive"))
      (node (ref "RHP1.1") (pin "1") (pinfunction "1_1") (pintype "passive"))
      (node (ref "RSTIM.1") (pin "2") (pinfunction "2_2") (pintype "passive"))
    )
    (net (code "65") (name "HIGHPASSOUT1.0") (class "Default")
      (node (ref "BANDPASSFILTER1.0") (pin "1") (pinfunction "OUT_A_1") (pintype "output"))
      (node (ref "BANDPASSFILTER1.0") (pin "2") (pinfunction "IN_A-_2") (pintype "passive"))
      (node (ref "RH1.0") (pin "1") (pinfunction "1_1") (pintype "passive"))
      (node (ref "RL1.0") (pin "1") (pinfunction "1_1") (pintype "passive"))
    )
    (net (code "66") (name "HIGHPASSOUT1.1") (class "Default")
      (node (ref "BANDPASSFILTER1.1") (pin "1") (pinfunction "OUT_A_1") (pintype "output"))
      (node (ref "BANDPASSFILTER1.1") (pin "2") (pinfunction "IN_A-_2") (pintype "passive"))
      (node (ref "RH1.1") (pin "1") (pinfunction "1_1") (pintype "passive"))
      (node (ref "RL1.1") (pin "1") (pinfunction "1_1") (pintype "passive"))
    )
    (net (code "67") (name "HIGHPASSOUT2.0") (class "Default")
      (node (ref "BANDPASSFILTER2.0") (pin "1") (pinfunction "OUT_A_1") (pintype "output"))
      (node (ref "BANDPASSFILTER2.0") (pin "2") (pinfunction "IN_A-_2") (pintype "passive"))
      (node (ref "RH3.0") (pin "1") (pinfunction "1_1") (pintype "passive"))
      (node (ref "RL4.0") (pin "1") (pinfunction "1_1") (pintype "passive"))
    )
    (net (code "68") (name "HIGHPASSOUT2.1") (class "Default")
      (node (ref "BANDPASSFILTER2.1") (pin "1") (pinfunction "OUT_A_1") (pintype "output"))
      (node (ref "BANDPASSFILTER2.1") (pin "2") (pinfunction "IN_A-_2") (pintype "passive"))
      (node (ref "RH3.1") (pin "1") (pinfunction "1_1") (pintype "passive"))
      (node (ref "RL3.1") (pin "1") (pinfunction "1_1") (pintype "passive"))
    )
    (net (code "69") (name "HPFINM0.0") (class "Default")
      (node (ref "CH1.0") (pin "2") (pinfunction "2_2") (pintype "passive"))
      (node (ref "CH2.0") (pin "2") (pinfunction "2_2") (pintype "passive"))
      (node (ref "RH1.0") (pin "2") (pinfunction "2_2") (pintype "passive"))
    )
    (net (code "70") (name "HPFINM0.1") (class "Default")
      (node (ref "CH1.1") (pin "1") (pinfunction "1_1") (pintype "passive"))
      (node (ref "CH2.1") (pin "1") (pinfunction "1_1") (pintype "passive"))
      (node (ref "RH1.1") (pin "2") (pinfunction "2_2") (pintype "passive"))
    )
    (net (code "71") (name "HPFINM1.0") (class "Default")
      (node (ref "CH3.0") (pin "2") (pinfunction "2_2") (pintype "passive"))
      (node (ref "CH4.0") (pin "2") (pinfunction "2_2") (pintype "passive"))
      (node (ref "RH3.0") (pin "2") (pinfunction "2_2") (pintype "passive"))
    )
    (net (code "72") (name "HPFINM1.1") (class "Default")
      (node (ref "CH3.1") (pin "1") (pinfunction "1_1") (pintype "passive"))
      (node (ref "CH4.1") (pin "1") (pinfunction "1_1") (pintype "passive"))
      (node (ref "RH3.1") (pin "2") (pinfunction "2_2") (pintype "passive"))
    )
    (net (code "73") (name "HPFINP0.0") (class "Default")
      (node (ref "BANDPASSFILTER1.0") (pin "3") (pinfunction "IN_A+_3") (pintype "input"))
      (node (ref "CH2.0") (pin "1") (pinfunction "1_1") (pintype "passive"))
      (node (ref "RH2.0") (pin "1") (pinfunction "1_1") (pintype "passive"))
    )
    (net (code "74") (name "HPFINP0.1") (class "Default")
      (node (ref "BANDPASSFILTER1.1") (pin "3") (pinfunction "IN_A+_3") (pintype "input"))
      (node (ref "CH2.1") (pin "2") (pinfunction "2_2") (pintype "passive"))
      (node (ref "RH2.1") (pin "2") (pinfunction "2_2") (pintype "passive"))
    )
    (net (code "75") (name "HPFINP1.0") (class "Default")
      (node (ref "BANDPASSFILTER2.0") (pin "3") (pinfunction "IN_A+_3") (pintype "input"))
      (node (ref "CH4.0") (pin "1") (pinfunction "1_1") (pintype "passive"))
      (node (ref "RH4.0") (pin "1") (pinfunction "1_1") (pintype "passive"))
    )
    (net (code "76") (name "HPFINP1.1") (class "Default")
      (node (ref "BANDPASSFILTER2.1") (pin "3") (pinfunction "IN_A+_3") (pintype "input"))
      (node (ref "CH4.1") (pin "2") (pinfunction "2_2") (pintype "passive"))
      (node (ref "RH4.1") (pin "2") (pinfunction "2_2") (pintype "passive"))
    )
    (net (code "77") (name "HP_IN.0") (class "Default")
      (node (ref "DAC.0") (pin "1") (pinfunction "VOUT_1") (pintype "output"))
      (node (ref "RHP2.0") (pin "2") (pinfunction "2_2") (pintype "passive"))
    )
    (net (code "78") (name "HP_IN.1") (class "Default")
      (node (ref "DAC.1") (pin "1") (pinfunction "VOUT_1") (pintype "output"))
      (node (ref "RHP2.1") (pin "2") (pinfunction "2_2") (pintype "passive"))
    )
    (net (code "79") (name "HP_OUT.0") (class "Default")
      (node (ref "HPAMPS.0") (pin "5") (pinfunction "IN2+_5") (pintype "tri_state"))
      (node (ref "OUTBUFFER.0") (pin "3") (pinfunction "IN+_3") (pintype "input"))
      (node (ref "RSTIM.0") (pin "2") (pinfunction "2_2") (pintype "passive"))
      (node (ref "U4") (pin "8") (pinfunction "S2_8") (pintype "bidirectional"))
      (node (ref "U5") (pin "8") (pinfunction "S2_8") (pintype "bidirectional"))
      (node (ref "U6") (pin "8") (pinfunction "S2_8") (pintype "bidirectional"))
      (node (ref "U7") (pin "8") (pinfunction "S2_8") (pintype "bidirectional"))
    )
    (net (code "80") (name "HP_OUT.1") (class "Default")
      (node (ref "HPAMPS.1") (pin "5") (pinfunction "IN2+_5") (pintype "tri_state"))
      (node (ref "OUTBUFFER.1") (pin "3") (pinfunction "IN+_3") (pintype "input"))
      (node (ref "RSTIM.1") (pin "1") (pinfunction "1_1") (pintype "passive"))
      (node (ref "U10") (pin "8") (pinfunction "S2_8") (pintype "bidirectional"))
      (node (ref "U11") (pin "8") (pinfunction "S2_8") (pintype "bidirectional"))
      (node (ref "U12") (pin "8") (pinfunction "S2_8") (pintype "bidirectional"))
      (node (ref "U8") (pin "8") (pinfunction "S2_8") (pintype "bidirectional"))
    )
    (net (code "81") (name "HP_OUT_BUF.0") (class "Default")
      (node (ref "OUTBUFFER.0") (pin "2") (pinfunction "IN-_2") (pintype "input"))
      (node (ref "OUTBUFFER.0") (pin "6") (pinfunction "OUT_6") (pintype "output"))
      (node (ref "RBOOT1.0") (pin "2") (pinfunction "2_2") (pintype "passive"))
      (node (ref "RBOOT2.0") (pin "1") (pinfunction "1_1") (pintype "passive"))
    )
    (net (code "82") (name "HP_OUT_BUF.1") (class "Default")
      (node (ref "OUTBUFFER.1") (pin "2") (pinfunction "IN-_2") (pintype "input"))
      (node (ref "OUTBUFFER.1") (pin "6") (pinfunction "OUT_6") (pintype "output"))
      (node (ref "RBOOT1.1") (pin "2") (pinfunction "2_2") (pintype "passive"))
      (node (ref "RBOOT2.1") (pin "1") (pinfunction "1_1") (pintype "passive"))
    )
    (net (code "83") (name "IN.0") (class "Default")
      (node (ref "CAC1.0") (pin "1") (pinfunction "1_1") (pintype "passive"))
      (node (ref "CRFI.0") (pin "2") (pinfunction "2_2") (pintype "passive"))
      (node (ref "U4") (pin "2") (pinfunction "S1_2") (pintype "bidirectional"))
      (node (ref "U5") (pin "2") (pinfunction "S1_2") (pintype "bidirectional"))
      (node (ref "U6") (pin "2") (pinfunction "S1_2") (pintype "bidirectional"))
      (node (ref "U7") (pin "2") (pinfunction "S1_2") (pintype "bidirectional"))
    )
    (net (code "84") (name "IN.1") (class "Default")
      (node (ref "CAC1.1") (pin "1") (pinfunction "1_1") (pintype "passive"))
      (node (ref "CRFI.1") (pin "1") (pinfunction "1_1") (pintype "passive"))
      (node (ref "U10") (pin "2") (pinfunction "S1_2") (pintype "bidirectional"))
      (node (ref "U11") (pin "2") (pinfunction "S1_2") (pintype "bidirectional"))
      (node (ref "U12") (pin "2") (pinfunction "S1_2") (pintype "bidirectional"))
      (node (ref "U8") (pin "2") (pinfunction "S1_2") (pintype "bidirectional"))
    )
    (net (code "85") (name "INM.0") (class "Default")
      (node (ref "CAC1.0") (pin "2") (pinfunction "2_2") (pintype "passive"))
      (node (ref "PREAMPLIFIER.0") (pin "2") (pinfunction "-IN_2") (pintype "input"))
      (node (ref "RAC1.0") (pin "2") (pinfunction "2_2") (pintype "passive"))
    )
    (net (code "86") (name "INM.1") (class "Default")
      (node (ref "CAC1.1") (pin "2") (pinfunction "2_2") (pintype "passive"))
      (node (ref "PREAMPLIFIER.1") (pin "2") (pinfunction "-IN_2") (pintype "input"))
      (node (ref "RAC1.1") (pin "2") (pinfunction "2_2") (pintype "passive"))
    )
    (net (code "87") (name "INP.0") (class "Default")
      (node (ref "CAC2.0") (pin "2") (pinfunction "2_2") (pintype "passive"))
      (node (ref "PREAMPLIFIER.0") (pin "3") (pinfunction "+IN_3") (pintype "input"))
      (node (ref "RAC2.0") (pin "1") (pinfunction "1_1") (pintype "passive"))
    )
    (net (code "88") (name "INP.1") (class "Default")
      (node (ref "CAC2.1") (pin "2") (pinfunction "2_2") (pintype "passive"))
      (node (ref "PREAMPLIFIER.1") (pin "3") (pinfunction "+IN_3") (pintype "input"))
      (node (ref "RAC2.1") (pin "1") (pinfunction "1_1") (pintype "passive"))
    )
    (net (code "89") (name "LPFINM0.0") (class "Default")
      (node (ref "CL1.0") (pin "2") (pinfunction "2_2") (pintype "passive"))
      (node (ref "RL1.0") (pin "2") (pinfunction "2_2") (pintype "passive"))
      (node (ref "RL2.0") (pin "1") (pinfunction "1_1") (pintype "passive"))
    )
    (net (code "90") (name "LPFINM0.1") (class "Default")
      (node (ref "CL1.1") (pin "1") (pinfunction "1_1") (pintype "passive"))
      (node (ref "RL1.1") (pin "2") (pinfunction "2_2") (pintype "passive"))
      (node (ref "RL2.1") (pin "1") (pinfunction "1_1") (pintype "passive"))
    )
    (net (code "91") (name "LPFINM1.0") (class "Default")
      (node (ref "CL3.0") (pin "2") (pinfunction "2_2") (pintype "passive"))
      (node (ref "RL3.0") (pin "1") (pinfunction "1_1") (pintype "passive"))
      (node (ref "RL4.0") (pin "2") (pinfunction "2_2") (pintype "passive"))
    )
    (net (code "92") (name "LPFINM1.1") (class "Default")
      (node (ref "CL3.1") (pin "1") (pinfunction "1_1") (pintype "passive"))
      (node (ref "RL3.1") (pin "2") (pinfunction "2_2") (pintype "passive"))
      (node (ref "RL4.1") (pin "1") (pinfunction "1_1") (pintype "passive"))
    )
    (net (code "93") (name "LPFINP0.0") (class "Default")
      (node (ref "BANDPASSFILTER1.0") (pin "5") (pinfunction "IN_B+_5") (pintype "input"))
      (node (ref "CL2.0") (pin "1") (pinfunction "1_1") (pintype "passive"))
      (node (ref "RL2.0") (pin "2") (pinfunction "2_2") (pintype "passive"))
    )
    (net (code "94") (name "LPFINP0.1") (class "Default")
      (node (ref "BANDPASSFILTER1.1") (pin "5") (pinfunction "IN_B+_5") (pintype "input"))
      (node (ref "CL2.1") (pin "2") (pinfunction "2_2") (pintype "passive"))
      (node (ref "RL2.1") (pin "2") (pinfunction "2_2") (pintype "passive"))
    )
    (net (code "95") (name "LPFINP1.0") (class "Default")
      (node (ref "BANDPASSFILTER2.0") (pin "5") (pinfunction "IN_B+_5") (pintype "input"))
      (node (ref "CL4.0") (pin "1") (pinfunction "1_1") (pintype "passive"))
      (node (ref "RL3.0") (pin "2") (pinfunction "2_2") (pintype "passive"))
    )
    (net (code "96") (name "LPFINP1.1") (class "Default")
      (node (ref "BANDPASSFILTER2.1") (pin "5") (pinfunction "IN_B+_5") (pintype "input"))
      (node (ref "CL4.1") (pin "2") (pinfunction "2_2") (pintype "passive"))
      (node (ref "RL4.1") (pin "2") (pinfunction "2_2") (pintype "passive"))
    )
    (net (code "97") (name "MID.0") (class "Default")
      (node (ref "RAC1.0") (pin "1") (pinfunction "1_1") (pintype "passive"))
      (node (ref "RAC2.0") (pin "2") (pinfunction "2_2") (pintype "passive"))
      (node (ref "RAC3.0") (pin "1") (pinfunction "1_1") (pintype "passive"))
    )
    (net (code "98") (name "MID.1") (class "Default")
      (node (ref "RAC1.1") (pin "1") (pinfunction "1_1") (pintype "passive"))
      (node (ref "RAC2.1") (pin "2") (pinfunction "2_2") (pintype "passive"))
      (node (ref "RAC3.1") (pin "1") (pinfunction "1_1") (pintype "passive"))
    )
    (net (code "99") (name "NA_REF.0") (class "Default")
      (node (ref "CL2.0") (pin "2") (pinfunction "2_2") (pintype "passive"))
      (node (ref "CL4.0") (pin "2") (pinfunction "2_2") (pintype "passive"))
      (node (ref "PGA.0") (pin "2") (pinfunction "AGND_2") (pintype "power_in"))
      (node (ref "PREAMPLIFIER.0") (pin "5") (pinfunction "REF_5") (pintype "input"))
      (node (ref "RAC3.0") (pin "2") (pinfunction "2_2") (pintype "passive"))
      (node (ref "RH2.0") (pin "2") (pinfunction "2_2") (pintype "passive"))
      (node (ref "RH4.0") (pin "2") (pinfunction "2_2") (pintype "passive"))
      (node (ref "RHP1.0") (pin "1") (pinfunction "1_1") (pintype "passive"))
      (node (ref "U1") (pin "6") (pinfunction "VO_6") (pintype "bidirectional"))
    )
    (net (code "100") (name "NA_REF.0.DIV") (class "Default")
      (node (ref "NAREFH.0") (pin "1") (pinfunction "1_1") (pintype "passive"))
      (node (ref "NAREFL.0") (pin "2") (pinfunction "2_2") (pintype "passive"))
      (node (ref "U1") (pin "3") (pinfunction "VIN_3") (pintype "input"))
    )
    (net (code "101") (name "NA_REF.1") (class "Default")
      (node (ref "CL2.1") (pin "1") (pinfunction "1_1") (pintype "passive"))
      (node (ref "CL4.1") (pin "1") (pinfunction "1_1") (pintype "passive"))
      (node (ref "PGA.1") (pin "2") (pinfunction "AGND_2") (pintype "power_in"))
      (node (ref "PREAMPLIFIER.1") (pin "5") (pinfunction "REF_5") (pintype "input"))
      (node (ref "RAC3.1") (pin "2") (pinfunction "2_2") (pintype "passive"))
      (node (ref "RH2.1") (pin "1") (pinfunction "1_1") (pintype "passive"))
      (node (ref "RH4.1") (pin "1") (pinfunction "1_1") (pintype "passive"))
      (node (ref "RHP0.1") (pin "2") (pinfunction "2_2") (pintype "passive"))
      (node (ref "U2") (pin "6") (pinfunction "VO_6") (pintype "bidirectional"))
    )
    (net (code "102") (name "NA_REF.1.DIV") (class "Default")
      (node (ref "NAREFH.1") (pin "1") (pinfunction "1_1") (pintype "passive"))
      (node (ref "NAREFL.1\\") (pin "2") (pinfunction "2_2") (pintype "passive"))
      (node (ref "U2") (pin "3") (pinfunction "VIN_3") (pintype "input"))
    )
    (net (code "103") (name "Net-(BOOSTFBPOT-Pad1)") (class "Default")
      (node (ref "BOOSTFBPOT") (pin "1") (pinfunction "1_1") (pintype "passive"))
      (node (ref "RBOOSTFB0") (pin "2") (pinfunction "2_2") (pintype "passive"))
    )
    (net (code "104") (name "PGAOUT1.0") (class "Default")
      (node (ref "CH3.0") (pin "1") (pinfunction "1_1") (pintype "passive"))
      (node (ref "PGA.0") (pin "10") (pinfunction "OUTA_10") (pintype "output"))
    )
    (net (code "105") (name "PGAOUT1.1") (class "Default")
      (node (ref "CH3.1") (pin "2") (pinfunction "2_2") (pintype "passive"))
      (node (ref "PGA.1") (pin "10") (pinfunction "OUTA_10") (pintype "output"))
    )
    (net (code "106") (name "PGAOUT2.0") (class "Default")
      (node (ref "ADC.0") (pin "6") (pinfunction "AINP_6") (pintype "input"))
      (node (ref "CADC.0") (pin "2") (pinfunction "2_2") (pintype "passive"))
      (node (ref "PGA.0") (pin "8") (pinfunction "OUTB_8") (pintype "output"))
    )
    (net (code "107") (name "PGAOUT2.1") (class "Default")
      (node (ref "ADC.1") (pin "6") (pinfunction "AINP_6") (pintype "input"))
      (node (ref "CADC.1") (pin "1") (pinfunction "1_1") (pintype "passive"))
      (node (ref "PGA.1") (pin "8") (pinfunction "OUTB_8") (pintype "output"))
    )
    (net (code "108") (name "PREAMPOUT.0") (class "Default")
      (node (ref "CH1.0") (pin "1") (pinfunction "1_1") (pintype "passive"))
      (node (ref "PREAMPLIFIER.0") (pin "6") (pinfunction "OUT_6") (pintype "output"))
    )
    (net (code "109") (name "PREAMPOUT.1") (class "Default")
      (node (ref "CH1.1") (pin "2") (pinfunction "2_2") (pintype "passive"))
      (node (ref "PREAMPLIFIER.1") (pin "6") (pinfunction "OUT_6") (pintype "output"))
    )
    (net (code "110") (name "REF.DIVIDE.0") (class "Default")
      (node (ref "AMPREF.0") (pin "3") (pinfunction "IN+_3") (pintype "input"))
      (node (ref "RBOOSTMID0.0") (pin "1") (pinfunction "1_1") (pintype "passive"))
      (node (ref "RBOOSTMID1.0") (pin "2") (pinfunction "2_2") (pintype "passive"))
    )
    (net (code "111") (name "REF.DIVIDE.1") (class "Default")
      (node (ref "AMPREF.1") (pin "3") (pinfunction "IN+_3") (pintype "input"))
      (node (ref "RBOOSTMID0.1") (pin "2") (pinfunction "2_2") (pintype "passive"))
      (node (ref "RBOOSTMID1.1") (pin "1") (pinfunction "1_1") (pintype "passive"))
    )
    (net (code "112") (name "REFOUT.0") (class "Default")
      (node (ref "AMPREF.0") (pin "2") (pinfunction "IN-_2") (pintype "input"))
      (node (ref "AMPREF.0") (pin "6") (pinfunction "OUT_6") (pintype "output"))
      (node (ref "CAC2.0") (pin "1") (pinfunction "1_1") (pintype "passive"))
      (node (ref "CREF2.0") (pin "1") (pinfunction "1_1") (pintype "passive"))
      (node (ref "CREF3.0") (pin "1") (pinfunction "1_1") (pintype "passive"))
      (node (ref "CRFI.0") (pin "1") (pinfunction "1_1") (pintype "passive"))
      (node (ref "J1") (pin "2") (pinfunction "2_2") (pintype "passive"))
      (node (ref "J1") (pin "4") (pinfunction "4_4") (pintype "passive"))
      (node (ref "J1") (pin "6") (pinfunction "6_6") (pintype "passive"))
      (node (ref "J1") (pin "8") (pinfunction "8_8") (pintype "passive"))
    )
    (net (code "113") (name "REFOUT.1") (class "Default")
      (node (ref "AMPREF.1") (pin "2") (pinfunction "IN-_2") (pintype "input"))
      (node (ref "AMPREF.1") (pin "6") (pinfunction "OUT_6") (pintype "output"))
      (node (ref "CAC2.1") (pin "1") (pinfunction "1_1") (pintype "passive"))
      (node (ref "CREF2.1") (pin "1") (pinfunction "1_1") (pintype "passive"))
      (node (ref "CREF3.1") (pin "1") (pinfunction "1_1") (pintype "passive"))
      (node (ref "CRFI.1") (pin "2") (pinfunction "2_2") (pintype "passive"))
      (node (ref "J2") (pin "2") (pinfunction "2_2") (pintype "passive"))
      (node (ref "J2") (pin "4") (pinfunction "4_4") (pintype "passive"))
      (node (ref "J2") (pin "6") (pinfunction "6_6") (pintype "passive"))
      (node (ref "J2") (pin "8") (pinfunction "8_8") (pintype "passive"))
    )
    (net (code "114") (name "VDD3.3") (class "Default")
      (node (ref "ADC.0") (pin "1") (pinfunction "DVDD_1") (pintype "power_in"))
      (node (ref "ADC.0") (pin "7") (pinfunction "AVDD_7") (pintype "power_in"))
      (node (ref "ADC.1") (pin "1") (pinfunction "DVDD_1") (pintype "power_in"))
      (node (ref "ADC.1") (pin "7") (pinfunction "AVDD_7") (pintype "power_in"))
      (node (ref "BANDPASSFILTER1.0") (pin "8") (pinfunction "V+_8") (pintype "power_in"))
      (node (ref "BANDPASSFILTER1.1") (pin "8") (pinfunction "V+_8") (pintype "power_in"))
      (node (ref "BANDPASSFILTER2.0") (pin "8") (pinfunction "V+_8") (pintype "power_in"))
      (node (ref "BANDPASSFILTER2.1") (pin "8") (pinfunction "V+_8") (pintype "power_in"))
      (node (ref "CDECAP0.0") (pin "1") (pinfunction "1_1") (pintype "passive"))
      (node (ref "CDECAP0.1") (pin "1") (pinfunction "1_1") (pintype "passive"))
      (node (ref "CDECAP1.0") (pin "1") (pinfunction "1_1") (pintype "passive"))
      (node (ref "CDECAP1.1") (pin "1") (pinfunction "1_1") (pintype "passive"))
      (node (ref "CDECAP2.0") (pin "1") (pinfunction "1_1") (pintype "passive"))
      (node (ref "CDECAP2.1") (pin "1") (pinfunction "1_1") (pintype "passive"))
      (node (ref "CDECAP3.0") (pin "1") (pinfunction "1_1") (pintype "passive"))
      (node (ref "CDECAP3.1") (pin "1") (pinfunction "1_1") (pintype "passive"))
      (node (ref "CDECAP4.0") (pin "1") (pinfunction "1_1") (pintype "passive"))
      (node (ref "CDECAP4.1") (pin "1") (pinfunction "1_1") (pintype "passive"))
      (node (ref "CDECAP5.0") (pin "1") (pinfunction "1_1") (pintype "passive"))
      (node (ref "CDECAP5.1") (pin "1") (pinfunction "1_1") (pintype "passive"))
      (node (ref "CDECAPREF.0") (pin "1") (pinfunction "1_1") (pintype "passive"))
      (node (ref "CDECAPREF.1") (pin "1") (pinfunction "1_1") (pintype "passive"))
      (node (ref "DAC.0") (pin "3") (pinfunction "VA_3") (pintype "power_in"))
      (node (ref "DAC.1") (pin "3") (pinfunction "VA_3") (pintype "power_in"))
      (node (ref "NAREFH.0") (pin "2") (pinfunction "2_2") (pintype "passive"))
      (node (ref "NAREFH.1") (pin "2") (pinfunction "2_2") (pintype "passive"))
      (node (ref "PGA.0") (pin "7") (pinfunction "V+_7") (pintype "power_in"))
      (node (ref "PGA.1") (pin "7") (pinfunction "V+_7") (pintype "power_in"))
      (node (ref "PREAMPLIFIER.0") (pin "7") (pinfunction "+VS_7") (pintype "passive"))
      (node (ref "PREAMPLIFIER.1") (pin "7") (pinfunction "+VS_7") (pintype "passive"))
      (node (ref "RADC.1") (pin "2") (pinfunction "2_2") (pintype "passive"))
      (node (ref "RADC.3") (pin "2") (pinfunction "2_2") (pintype "passive"))
      (node (ref "RDAC.1") (pin "1") (pinfunction "1_1") (pintype "passive"))
      (node (ref "RDAC.2") (pin "1") (pinfunction "1_1") (pintype "passive"))
      (node (ref "U$2") (pin "09") (pinfunction "+3.3VDD_09") (pintype "bidirectional"))
      (node (ref "U$2") (pin "11") (pinfunction "+3.3VDD.1_11") (pintype "bidirectional"))
      (node (ref "U$2") (pin "13") (pinfunction "+3.3VDD.2_13") (pintype "bidirectional"))
      (node (ref "U$2") (pin "82") (pinfunction "+3.3VDD.3_82") (pintype "bidirectional"))
      (node (ref "U$2") (pin "84") (pinfunction "+3.3VDD.4_84") (pintype "bidirectional"))
      (node (ref "U$2") (pin "86") (pinfunction "+3.3VDD.5_86") (pintype "bidirectional"))
      (node (ref "U1") (pin "7") (pinfunction "V+_7") (pintype "power_in"))
      (node (ref "U2") (pin "7") (pinfunction "V+_7") (pintype "power_in"))
    )
    (net (code "115") (name "VDD5.0") (class "Default")
      (node (ref "BOOSTCTRL") (pin "2") (pinfunction "VCC_2") (pintype "passive"))
      (node (ref "BOOSTCTRL") (pin "3") (pinfunction "BIAS_3") (pintype "power_in"))
      (node (ref "BOOSTCTRL") (pin "6") (pinfunction "EN_UVLO_SYNC_6") (pintype "input"))
      (node (ref "CBIAS") (pin "1") (pinfunction "1_1") (pintype "passive"))
      (node (ref "CDECAPXEM0") (pin "1") (pinfunction "1_1") (pintype "passive"))
      (node (ref "CDECAPXEM1") (pin "1") (pinfunction "1_1") (pintype "passive"))
      (node (ref "CDECAPXEM2") (pin "1") (pinfunction "1_1") (pintype "passive"))
      (node (ref "CVDD") (pin "1") (pinfunction "1_1") (pintype "passive"))
      (node (ref "U$1") (pin "P$1") (pinfunction "P$1_P$1") (pintype "bidirectional"))
      (node (ref "U$2") (pin "01") (pinfunction "+VDCIN_01") (pintype "bidirectional"))
      (node (ref "U$2") (pin "03") (pinfunction "+VDCIN.1_03") (pintype "bidirectional"))
      (node (ref "U$2") (pin "05") (pinfunction "+VDCIN.2_05") (pintype "bidirectional"))
    )
    (net (code "116") (name "VDDHP.0") (class "Default")
      (node (ref "BOOTSTRAP.0") (pin "1") (pinfunction "NS2_1") (pintype "passive"))
      (node (ref "CDECAP6.0") (pin "1") (pinfunction "1_1") (pintype "passive"))
      (node (ref "CDECAP7.0") (pin "1") (pinfunction "1_1") (pintype "passive"))
      (node (ref "CDECAP7.2") (pin "1") (pinfunction "1_1") (pintype "passive"))
      (node (ref "HPAMPS.0") (pin "8") (pinfunction "V+_8") (pintype "power_in"))
      (node (ref "OUTBUFFER.0") (pin "7") (pinfunction "V+_7") (pintype "power_in"))
      (node (ref "RBYPASSVDD") (pin "2") (pinfunction "2_2") (pintype "passive"))
    )
    (net (code "117") (name "VDDHP.1") (class "Default")
      (node (ref "BOOTSTRAPPER.1") (pin "1") (pinfunction "NS2_1") (pintype "passive"))
      (node (ref "CDECAP6.1") (pin "1") (pinfunction "1_1") (pintype "passive"))
      (node (ref "CDECAP7.1") (pin "1") (pinfunction "1_1") (pintype "passive"))
      (node (ref "CDECAP7.3") (pin "1") (pinfunction "1_1") (pintype "passive"))
      (node (ref "HPAMPS.1") (pin "8") (pinfunction "V+_8") (pintype "power_in"))
      (node (ref "OUTBUFFER.1") (pin "7") (pinfunction "V+_7") (pintype "power_in"))
      (node (ref "RBYPASSVDD.1") (pin "2") (pinfunction "2_2") (pintype "passive"))
    )
    (net (code "118") (name "VDDHV") (class "Default")
      (node (ref "AMPREF.0") (pin "7") (pinfunction "V+_7") (pintype "power_in"))
      (node (ref "AMPREF.1") (pin "7") (pinfunction "V+_7") (pintype "power_in"))
      (node (ref "BOOTSTRAP.0") (pin "7") (pinfunction "ND2_2_7") (pintype "passive"))
      (node (ref "BOOTSTRAP.0") (pin "8") (pinfunction "ND2_8") (pintype "passive"))
      (node (ref "BOOTSTRAPPER.1") (pin "7") (pinfunction "ND2_2_7") (pintype "passive"))
      (node (ref "BOOTSTRAPPER.1") (pin "8") (pinfunction "ND2_8") (pintype "passive"))
      (node (ref "CCH1.0") (pin "1") (pinfunction "1_1") (pintype "passive"))
      (node (ref "CCH2.0") (pin "1") (pinfunction "1_1") (pintype "passive"))
      (node (ref "CCH3.0") (pin "1") (pinfunction "1_1") (pintype "passive"))
      (node (ref "CCH4.0") (pin "1") (pinfunction "1_1") (pintype "passive"))
      (node (ref "CCH5.1") (pin "1") (pinfunction "1_1") (pintype "passive"))
      (node (ref "CCH6.1") (pin "1") (pinfunction "1_1") (pintype "passive"))
      (node (ref "CCH7.1") (pin "1") (pinfunction "1_1") (pintype "passive"))
      (node (ref "CCH8.1") (pin "1") (pinfunction "1_1") (pintype "passive"))
      (node (ref "CDECAP8.0") (pin "1") (pinfunction "1_1") (pintype "passive"))
      (node (ref "CDECAP8.1") (pin "1") (pinfunction "1_1") (pintype "passive"))
      (node (ref "CDECAP9.0") (pin "1") (pinfunction "1_1") (pintype "passive"))
      (node (ref "CDECAP9.1") (pin "1") (pinfunction "1_1") (pintype "passive"))
      (node (ref "COUT1") (pin "1") (pinfunction "1_1") (pintype "passive"))
      (node (ref "COUT2") (pin "1") (pinfunction "1_1") (pintype "passive"))
      (node (ref "COUT3") (pin "1") (pinfunction "1_1") (pintype "passive"))
      (node (ref "CREF0.0") (pin "1") (pinfunction "1_1") (pintype "passive"))
      (node (ref "CREF0.1") (pin "1") (pinfunction "1_1") (pintype "passive"))
      (node (ref "CREF1.0") (pin "1") (pinfunction "1_1") (pintype "passive"))
      (node (ref "CREF1.1") (pin "1") (pinfunction "1_1") (pintype "passive"))
      (node (ref "D1") (pin "1") (pinfunction "1_1") (pintype "passive"))
      (node (ref "J4") (pin "1") (pinfunction "1_1") (pintype "passive"))
      (node (ref "RBOOSTFB1") (pin "2") (pinfunction "2_2") (pintype "passive"))
      (node (ref "RBOOSTMID0.0") (pin "2") (pinfunction "2_2") (pintype "passive"))
      (node (ref "RBOOSTMID1.1") (pin "2") (pinfunction "2_2") (pintype "passive"))
      (node (ref "RBOOT3.0") (pin "2") (pinfunction "2_2") (pintype "passive"))
      (node (ref "RBOOT3.1") (pin "2") (pinfunction "2_2") (pintype "passive"))
      (node (ref "RBYPASSVDD") (pin "1") (pinfunction "1_1") (pintype "passive"))
      (node (ref "RBYPASSVDD.1") (pin "1") (pinfunction "1_1") (pintype "passive"))
      (node (ref "U10") (pin "4") (pinfunction "VDD_4") (pintype "power_in"))
      (node (ref "U11") (pin "4") (pinfunction "VDD_4") (pintype "power_in"))
      (node (ref "U12") (pin "4") (pinfunction "VDD_4") (pintype "power_in"))
      (node (ref "U4") (pin "4") (pinfunction "VDD_4") (pintype "power_in"))
      (node (ref "U5") (pin "4") (pinfunction "VDD_4") (pintype "power_in"))
      (node (ref "U6") (pin "4") (pinfunction "VDD_4") (pintype "power_in"))
      (node (ref "U7") (pin "4") (pinfunction "VDD_4") (pintype "power_in"))
      (node (ref "U8") (pin "4") (pinfunction "VDD_4") (pintype "power_in"))
    )
    (net (code "119") (name "VDDHV_BYPASS") (class "Default")
      (node (ref "J4") (pin "2") (pinfunction "2_2") (pintype "passive"))
      (node (ref "J4") (pin "3") (pinfunction "3_3") (pintype "passive"))
    )
    (net (code "120") (name "VSS") (class "Default")
      (node (ref "ADC.0") (pin "5") (pinfunction "AINM_5") (pintype "input"))
      (node (ref "ADC.0") (pin "8") (pinfunction "GND_8") (pintype "power_in"))
      (node (ref "ADC.1") (pin "5") (pinfunction "AINM_5") (pintype "input"))
      (node (ref "ADC.1") (pin "8") (pinfunction "GND_8") (pintype "power_in"))
      (node (ref "AMPREF.0") (pin "1") (pinfunction "V-_2_1") (pintype "power_in"))
      (node (ref "AMPREF.0") (pin "4") (pinfunction "V-_3_4") (pintype "power_in"))
      (node (ref "AMPREF.0") (pin "5") (pinfunction "V-_5") (pintype "power_in"))
      (node (ref "AMPREF.1") (pin "1") (pinfunction "V-_2_1") (pintype "power_in"))
      (node (ref "AMPREF.1") (pin "4") (pinfunction "V-_3_4") (pintype "power_in"))
      (node (ref "AMPREF.1") (pin "5") (pinfunction "V-_5") (pintype "power_in"))
      (node (ref "BANDPASSFILTER1.0") (pin "4") (pinfunction "V-_4") (pintype "passive"))
      (node (ref "BANDPASSFILTER1.1") (pin "4") (pinfunction "V-_4") (pintype "passive"))
      (node (ref "BANDPASSFILTER2.0") (pin "4") (pinfunction "V-_4") (pintype "passive"))
      (node (ref "BANDPASSFILTER2.1") (pin "4") (pinfunction "V-_4") (pintype "passive"))
      (node (ref "BOOSTCTRL") (pin "1") (pinfunction "PGND_2_1") (pintype "power_in"))
      (node (ref "BOOSTCTRL") (pin "11") (pinfunction "MODE_11") (pintype "passive"))
      (node (ref "BOOSTCTRL") (pin "16") (pinfunction "PGND_16") (pintype "power_in"))
      (node (ref "BOOSTCTRL") (pin "17") (pinfunction "EP_17") (pintype "power_in"))
      (node (ref "BOOSTCTRL") (pin "7") (pinfunction "AGND_7") (pintype "power_in"))
      (node (ref "BOOTSTRAP.0") (pin "5") (pinfunction "PD1_2_5") (pintype "passive"))
      (node (ref "BOOTSTRAP.0") (pin "6") (pinfunction "PD1_6") (pintype "passive"))
      (node (ref "BOOTSTRAPPER.1") (pin "5") (pinfunction "PD1_2_5") (pintype "passive"))
      (node (ref "BOOTSTRAPPER.1") (pin "6") (pinfunction "PD1_6") (pintype "passive"))
      (node (ref "CADC.0") (pin "1") (pinfunction "1_1") (pintype "passive"))
      (node (ref "CADC.1") (pin "2") (pinfunction "2_2") (pintype "passive"))
      (node (ref "CBIAS") (pin "2") (pinfunction "2_2") (pintype "passive"))
      (node (ref "CCH1.0") (pin "2") (pinfunction "2_2") (pintype "passive"))
      (node (ref "CCH2.0") (pin "2") (pinfunction "2_2") (pintype "passive"))
      (node (ref "CCH3.0") (pin "2") (pinfunction "2_2") (pintype "passive"))
      (node (ref "CCH4.0") (pin "2") (pinfunction "2_2") (pintype "passive"))
      (node (ref "CCH5.1") (pin "2") (pinfunction "2_2") (pintype "passive"))
      (node (ref "CCH6.1") (pin "2") (pinfunction "2_2") (pintype "passive"))
      (node (ref "CCH7.1") (pin "2") (pinfunction "2_2") (pintype "passive"))
      (node (ref "CCH8.1") (pin "2") (pinfunction "2_2") (pintype "passive"))
      (node (ref "CCOMP") (pin "2") (pinfunction "2_2") (pintype "passive"))
      (node (ref "CCOMP1") (pin "2") (pinfunction "2_2") (pintype "passive"))
      (node (ref "CDECAP0.0") (pin "2") (pinfunction "2_2") (pintype "passive"))
      (node (ref "CDECAP0.1") (pin "2") (pinfunction "2_2") (pintype "passive"))
      (node (ref "CDECAP1.0") (pin "2") (pinfunction "2_2") (pintype "passive"))
      (node (ref "CDECAP1.1") (pin "2") (pinfunction "2_2") (pintype "passive"))
      (node (ref "CDECAP2.0") (pin "2") (pinfunction "2_2") (pintype "passive"))
      (node (ref "CDECAP2.1") (pin "2") (pinfunction "2_2") (pintype "passive"))
      (node (ref "CDECAP3.0") (pin "2") (pinfunction "2_2") (pintype "passive"))
      (node (ref "CDECAP3.1") (pin "2") (pinfunction "2_2") (pintype "passive"))
      (node (ref "CDECAP4.0") (pin "2") (pinfunction "2_2") (pintype "passive"))
      (node (ref "CDECAP4.1") (pin "2") (pinfunction "2_2") (pintype "passive"))
      (node (ref "CDECAP5.0") (pin "2") (pinfunction "2_2") (pintype "passive"))
      (node (ref "CDECAP5.1") (pin "2") (pinfunction "2_2") (pintype "passive"))
      (node (ref "CDECAP8.0") (pin "2") (pinfunction "2_2") (pintype "passive"))
      (node (ref "CDECAP8.1") (pin "2") (pinfunction "2_2") (pintype "passive"))
      (node (ref "CDECAP9.0") (pin "2") (pinfunction "2_2") (pintype "passive"))
      (node (ref "CDECAP9.1") (pin "2") (pinfunction "2_2") (pintype "passive"))
      (node (ref "CDECAPREF.0") (pin "2") (pinfunction "2_2") (pintype "passive"))
      (node (ref "CDECAPREF.1") (pin "2") (pinfunction "2_2") (pintype "passive"))
      (node (ref "CDECAPXEM0") (pin "2") (pinfunction "2_2") (pintype "passive"))
      (node (ref "CDECAPXEM1") (pin "2") (pinfunction "2_2") (pintype "passive"))
      (node (ref "CDECAPXEM2") (pin "2") (pinfunction "2_2") (pintype "passive"))
      (node (ref "COUT1") (pin "2") (pinfunction "2_2") (pintype "passive"))
      (node (ref "COUT2") (pin "2") (pinfunction "2_2") (pintype "passive"))
      (node (ref "COUT3") (pin "2") (pinfunction "2_2") (pintype "passive"))
      (node (ref "CREF0.0") (pin "2") (pinfunction "2_2") (pintype "passive"))
      (node (ref "CREF0.1") (pin "2") (pinfunction "2_2") (pintype "passive"))
      (node (ref "CREF1.0") (pin "2") (pinfunction "2_2") (pintype "passive"))
      (node (ref "CREF1.1") (pin "2") (pinfunction "2_2") (pintype "passive"))
      (node (ref "CREF2.0") (pin "2") (pinfunction "2_2") (pintype "passive"))
      (node (ref "CREF2.1") (pin "2") (pinfunction "2_2") (pintype "passive"))
      (node (ref "CREF3.0") (pin "2") (pinfunction "2_2") (pintype "passive"))
      (node (ref "CREF3.1") (pin "2") (pinfunction "2_2") (pintype "passive"))
      (node (ref "CSS") (pin "2") (pinfunction "2_2") (pintype "passive"))
      (node (ref "CVDD") (pin "2") (pinfunction "2_2") (pintype "passive"))
      (node (ref "DAC.0") (pin "2") (pinfunction "GND_2") (pintype "power_in"))
      (node (ref "DAC.1") (pin "2") (pinfunction "GND_2") (pintype "power_in"))
      (node (ref "J3") (pin "1") (pinfunction "1_1") (pintype "passive"))
      (node (ref "NAREFL.0") (pin "1") (pinfunction "1_1") (pintype "passive"))
      (node (ref "NAREFL.1\\") (pin "1") (pinfunction "1_1") (pintype "passive"))
      (node (ref "PGA.0") (pin "9") (pinfunction "V-_9") (pintype "power_in"))
      (node (ref "PGA.1") (pin "9") (pinfunction "V-_9") (pintype "power_in"))
      (node (ref "PREAMPLIFIER.0") (pin "4") (pinfunction "-VS_4") (pintype "passive"))
      (node (ref "PREAMPLIFIER.1") (pin "4") (pinfunction "-VS_4") (pintype "passive"))
      (node (ref "RBOOSTFB0") (pin "1") (pinfunction "1_1") (pintype "passive"))
      (node (ref "RBOOSTMID0.1") (pin "1") (pinfunction "1_1") (pintype "passive"))
      (node (ref "RBOOSTMID1.0") (pin "1") (pinfunction "1_1") (pintype "passive"))
      (node (ref "RBOOT0.0") (pin "1") (pinfunction "1_1") (pintype "passive"))
      (node (ref "RBOOT0.1") (pin "1") (pinfunction "1_1") (pintype "passive"))
      (node (ref "RBYPASSVSS") (pin "1") (pinfunction "1_1") (pintype "passive"))
      (node (ref "RBYPASSVSS.1") (pin "1") (pinfunction "1_1") (pintype "passive"))
      (node (ref "RCH.40") (pin "2") (pinfunction "2_2") (pintype "passive"))
      (node (ref "RCH1.0") (pin "2") (pinfunction "2_2") (pintype "passive"))
      (node (ref "RCH2.0") (pin "2") (pinfunction "2_2") (pintype "passive"))
      (node (ref "RCH3.0") (pin "2") (pinfunction "2_2") (pintype "passive"))
      (node (ref "RCH5.0") (pin "2") (pinfunction "2_2") (pintype "passive"))
      (node (ref "RCH6.0") (pin "2") (pinfunction "2_2") (pintype "passive"))
      (node (ref "RCH7.0") (pin "2") (pinfunction "2_2") (pintype "passive"))
      (node (ref "RCH8.0") (pin "2") (pinfunction "2_2") (pintype "passive"))
      (node (ref "RT") (pin "2") (pinfunction "2_2") (pintype "passive"))
      (node (ref "U$2") (pin "02") (pinfunction "DGND_02") (pintype "bidirectional"))
      (node (ref "U$2") (pin "116") (pinfunction "DGND.9_116") (pintype "bidirectional"))
      (node (ref "U$2") (pin "136") (pinfunction "DGND.10_136") (pintype "bidirectional"))
      (node (ref "U$2") (pin "14") (pinfunction "DGND.1_14") (pintype "bidirectional"))
      (node (ref "U$2") (pin "158") (pinfunction "DGND.11_158") (pintype "bidirectional"))
      (node (ref "U$2") (pin "160") (pinfunction "DGND.12_160") (pintype "bidirectional"))
      (node (ref "U$2") (pin "35") (pinfunction "DGND.2_35") (pintype "bidirectional"))
      (node (ref "U$2") (pin "55") (pinfunction "DGND.3_55") (pintype "bidirectional"))
      (node (ref "U$2") (pin "78") (pinfunction "DGND.4_78") (pintype "bidirectional"))
      (node (ref "U$2") (pin "80") (pinfunction "DGND.5_80") (pintype "bidirectional"))
      (node (ref "U$2") (pin "81") (pinfunction "DGND.6_81") (pintype "bidirectional"))
      (node (ref "U$2") (pin "93") (pinfunction "DGND.7_93") (pintype "bidirectional"))
      (node (ref "U$2") (pin "94") (pinfunction "DGND.8_94") (pintype "bidirectional"))
      (node (ref "U1") (pin "4") (pinfunction "V__4") (pintype "bidirectional"))
      (node (ref "U10") (pin "3") (pinfunction "GND_3") (pintype "passive"))
      (node (ref "U10") (pin "7") (pinfunction "VSS_7") (pintype "passive"))
      (node (ref "U11") (pin "3") (pinfunction "GND_3") (pintype "passive"))
      (node (ref "U11") (pin "7") (pinfunction "VSS_7") (pintype "passive"))
      (node (ref "U12") (pin "3") (pinfunction "GND_3") (pintype "passive"))
      (node (ref "U12") (pin "7") (pinfunction "VSS_7") (pintype "passive"))
      (node (ref "U2") (pin "4") (pinfunction "V__4") (pintype "bidirectional"))
      (node (ref "U4") (pin "3") (pinfunction "GND_3") (pintype "passive"))
      (node (ref "U4") (pin "7") (pinfunction "VSS_7") (pintype "passive"))
      (node (ref "U5") (pin "3") (pinfunction "GND_3") (pintype "passive"))
      (node (ref "U5") (pin "7") (pinfunction "VSS_7") (pintype "passive"))
      (node (ref "U6") (pin "3") (pinfunction "GND_3") (pintype "passive"))
      (node (ref "U6") (pin "7") (pinfunction "VSS_7") (pintype "passive"))
      (node (ref "U7") (pin "3") (pinfunction "GND_3") (pintype "passive"))
      (node (ref "U7") (pin "7") (pinfunction "VSS_7") (pintype "passive"))
      (node (ref "U8") (pin "3") (pinfunction "GND_3") (pintype "passive"))
      (node (ref "U8") (pin "7") (pinfunction "VSS_7") (pintype "passive"))
    )
    (net (code "121") (name "VSSHP.0") (class "Default")
      (node (ref "BOOTSTRAP.0") (pin "3") (pinfunction "PS1_3") (pintype "passive"))
      (node (ref "CDECAP6.0") (pin "2") (pinfunction "2_2") (pintype "passive"))
      (node (ref "CDECAP7.0") (pin "2") (pinfunction "2_2") (pintype "passive"))
      (node (ref "CDECAP7.2") (pin "2") (pinfunction "2_2") (pintype "passive"))
      (node (ref "HPAMPS.0") (pin "4") (pinfunction "V-_4") (pintype "power_in"))
      (node (ref "OUTBUFFER.0") (pin "1") (pinfunction "V-_2_1") (pintype "power_in"))
      (node (ref "OUTBUFFER.0") (pin "4") (pinfunction "V-_3_4") (pintype "power_in"))
      (node (ref "OUTBUFFER.0") (pin "5") (pinfunction "V-_5") (pintype "power_in"))
      (node (ref "RBYPASSVSS") (pin "2") (pinfunction "2_2") (pintype "passive"))
    )
    (net (code "122") (name "VSSHP.1") (class "Default")
      (node (ref "BOOTSTRAPPER.1") (pin "3") (pinfunction "PS1_3") (pintype "passive"))
      (node (ref "CDECAP6.1") (pin "2") (pinfunction "2_2") (pintype "passive"))
      (node (ref "CDECAP7.1") (pin "2") (pinfunction "2_2") (pintype "passive"))
      (node (ref "CDECAP7.3") (pin "2") (pinfunction "2_2") (pintype "passive"))
      (node (ref "HPAMPS.1") (pin "4") (pinfunction "V-_4") (pintype "power_in"))
      (node (ref "OUTBUFFER.1") (pin "1") (pinfunction "V-_2_1") (pintype "power_in"))
      (node (ref "OUTBUFFER.1") (pin "4") (pinfunction "V-_3_4") (pintype "power_in"))
      (node (ref "OUTBUFFER.1") (pin "5") (pinfunction "V-_5") (pintype "power_in"))
      (node (ref "RBYPASSVSS.1") (pin "2") (pinfunction "2_2") (pintype "passive"))
    )
    (net (code "123") (name "VSS_BYPASS") (class "Default")
      (node (ref "J3") (pin "2") (pinfunction "2_2") (pintype "passive"))
      (node (ref "J3") (pin "3") (pinfunction "3_3") (pintype "passive"))
    )
    (net (code "124") (name "unconnected-(AMPREF.0-FLAG-Pad8)") (class "Default")
      (node (ref "AMPREF.0") (pin "8") (pinfunction "FLAG_8") (pintype "passive"))
    )
    (net (code "125") (name "unconnected-(AMPREF.1-FLAG-Pad8)") (class "Default")
      (node (ref "AMPREF.1") (pin "8") (pinfunction "FLAG_8") (pintype "passive"))
    )
    (net (code "126") (name "unconnected-(BOOSTCTRL-NC-Pad15)") (class "Default")
      (node (ref "BOOSTCTRL") (pin "15") (pinfunction "NC_15") (pintype "passive"))
    )
    (net (code "127") (name "unconnected-(BOOSTCTRL-NC_2-Pad12)") (class "Default")
      (node (ref "BOOSTCTRL") (pin "12") (pinfunction "NC_2_12") (pintype "passive"))
    )
    (net (code "128") (name "unconnected-(BOOSTCTRL-PGOOD-Pad4)") (class "Default")
      (node (ref "BOOSTCTRL") (pin "4") (pinfunction "PGOOD_4") (pintype "open_collector"))
    )
    (net (code "129") (name "unconnected-(BOOSTFBPOT-Pad3)") (class "Default")
      (node (ref "BOOSTFBPOT") (pin "3") (pinfunction "3_3") (pintype "passive"))
    )
    (net (code "130") (name "unconnected-(OUTBUFFER.0-FLAG-Pad8)") (class "Default")
      (node (ref "OUTBUFFER.0") (pin "8") (pinfunction "FLAG_8") (pintype "passive"))
    )
    (net (code "131") (name "unconnected-(OUTBUFFER.1-FLAG-Pad8)") (class "Default")
      (node (ref "OUTBUFFER.1") (pin "8") (pinfunction "FLAG_8") (pintype "passive"))
    )
    (net (code "132") (name "unconnected-(U$2-+1.0VDD-Pad04)") (class "Default")
      (node (ref "U$2") (pin "04") (pinfunction "+1.0VDD_04") (pintype "bidirectional"))
    )
    (net (code "133") (name "unconnected-(U$2-+1.0VDD.1-Pad06)") (class "Default")
      (node (ref "U$2") (pin "06") (pinfunction "+1.0VDD.1_06") (pintype "bidirectional"))
    )
    (net (code "134") (name "unconnected-(U$2-+1.8VDD-Pad07)") (class "Default")
      (node (ref "U$2") (pin "07") (pinfunction "+1.8VDD_07") (pintype "bidirectional"))
    )
    (net (code "135") (name "unconnected-(U$2-+VCCBATT-Pad83)") (class "Default")
      (node (ref "U$2") (pin "83") (pinfunction "+VCCBATT_83") (pintype "bidirectional"))
    )
    (net (code "136") (name "unconnected-(U$2-A1-Pad141)") (class "Default")
      (node (ref "U$2") (pin "141") (pinfunction "A1_141") (pintype "bidirectional"))
    )
    (net (code "137") (name "unconnected-(U$2-AA3-Pad47)") (class "Default")
      (node (ref "U$2") (pin "47") (pinfunction "AA3_47") (pintype "bidirectional"))
    )
    (net (code "138") (name "unconnected-(U$2-AA4-Pad40)") (class "Default")
      (node (ref "U$2") (pin "40") (pinfunction "AA4_40") (pintype "bidirectional"))
    )
    (net (code "139") (name "unconnected-(U$2-AA5-Pad31)") (class "Default")
      (node (ref "U$2") (pin "31") (pinfunction "AA5_31") (pintype "bidirectional"))
    )
    (net (code "140") (name "unconnected-(U$2-AA6-Pad44)") (class "Default")
      (node (ref "U$2") (pin "44") (pinfunction "AA6_44") (pintype "bidirectional"))
    )
    (net (code "141") (name "unconnected-(U$2-AA8-Pad46)") (class "Default")
      (node (ref "U$2") (pin "46") (pinfunction "AA8_46") (pintype "bidirectional"))
    )
    (net (code "142") (name "unconnected-(U$2-AA13-Pad68)") (class "Default")
      (node (ref "U$2") (pin "68") (pinfunction "AA13_68") (pintype "bidirectional"))
    )
    (net (code "143") (name "unconnected-(U$2-AA14-Pad66)") (class "Default")
      (node (ref "U$2") (pin "66") (pinfunction "AA14_66") (pintype "bidirectional"))
    )
    (net (code "144") (name "unconnected-(U$2-AA16-Pad76)") (class "Default")
      (node (ref "U$2") (pin "76") (pinfunction "AA16_76") (pintype "bidirectional"))
    )
    (net (code "145") (name "unconnected-(U$2-AB2-Pad62)") (class "Default")
      (node (ref "U$2") (pin "62") (pinfunction "AB2_62") (pintype "bidirectional"))
    )
    (net (code "146") (name "unconnected-(U$2-AB3-Pad60)") (class "Default")
      (node (ref "U$2") (pin "60") (pinfunction "AB3_60") (pintype "bidirectional"))
    )
    (net (code "147") (name "unconnected-(U$2-AB5-Pad33)") (class "Default")
      (node (ref "U$2") (pin "33") (pinfunction "AB5_33") (pintype "bidirectional"))
    )
    (net (code "148") (name "unconnected-(U$2-AB6-Pad39)") (class "Default")
      (node (ref "U$2") (pin "39") (pinfunction "AB6_39") (pintype "bidirectional"))
    )
    (net (code "149") (name "unconnected-(U$2-AB7-Pad37)") (class "Default")
      (node (ref "U$2") (pin "37") (pinfunction "AB7_37") (pintype "bidirectional"))
    )
    (net (code "150") (name "unconnected-(U$2-AB8-Pad48)") (class "Default")
      (node (ref "U$2") (pin "48") (pinfunction "AB8_48") (pintype "bidirectional"))
    )
    (net (code "151") (name "unconnected-(U$2-AB11-Pad08)") (class "Default")
      (node (ref "U$2") (pin "08") (pinfunction "AB11_08") (pintype "bidirectional"))
    )
    (net (code "152") (name "unconnected-(U$2-AB12-Pad91)") (class "Default")
      (node (ref "U$2") (pin "91") (pinfunction "AB12_91") (pintype "bidirectional"))
    )
    (net (code "153") (name "unconnected-(U$2-AB13-Pad70)") (class "Default")
      (node (ref "U$2") (pin "70") (pinfunction "AB13_70") (pintype "bidirectional"))
    )
    (net (code "154") (name "unconnected-(U$2-AB16-Pad67)") (class "Default")
      (node (ref "U$2") (pin "67") (pinfunction "AB16_67") (pintype "bidirectional"))
    )
    (net (code "155") (name "unconnected-(U$2-AB17-Pad69)") (class "Default")
      (node (ref "U$2") (pin "69") (pinfunction "AB17_69") (pintype "bidirectional"))
    )
    (net (code "156") (name "unconnected-(U$2-B1-Pad139)") (class "Default")
      (node (ref "U$2") (pin "139") (pinfunction "B1_139") (pintype "bidirectional"))
    )
    (net (code "157") (name "unconnected-(U$2-B2-Pad142)") (class "Default")
      (node (ref "U$2") (pin "142") (pinfunction "B2_142") (pintype "bidirectional"))
    )
    (net (code "158") (name "unconnected-(U$2-C2-Pad140)") (class "Default")
      (node (ref "U$2") (pin "140") (pinfunction "C2_140") (pintype "bidirectional"))
    )
    (net (code "159") (name "unconnected-(U$2-D1-Pad138)") (class "Default")
      (node (ref "U$2") (pin "138") (pinfunction "D1_138") (pintype "bidirectional"))
    )
    (net (code "160") (name "unconnected-(U$2-D2-Pad131)") (class "Default")
      (node (ref "U$2") (pin "131") (pinfunction "D2_131") (pintype "bidirectional"))
    )
    (net (code "161") (name "unconnected-(U$2-E1-Pad134)") (class "Default")
      (node (ref "U$2") (pin "134") (pinfunction "E1_134") (pintype "bidirectional"))
    )
    (net (code "162") (name "unconnected-(U$2-E2-Pad129)") (class "Default")
      (node (ref "U$2") (pin "129") (pinfunction "E2_129") (pintype "bidirectional"))
    )
    (net (code "163") (name "unconnected-(U$2-E3-Pad137)") (class "Default")
      (node (ref "U$2") (pin "137") (pinfunction "E3_137") (pintype "bidirectional"))
    )
    (net (code "164") (name "unconnected-(U$2-F1-Pad132)") (class "Default")
      (node (ref "U$2") (pin "132") (pinfunction "F1_132") (pintype "bidirectional"))
    )
    (net (code "165") (name "unconnected-(U$2-F3-Pad133)") (class "Default")
      (node (ref "U$2") (pin "133") (pinfunction "F3_133") (pintype "bidirectional"))
    )
    (net (code "166") (name "unconnected-(U$2-F4-Pad90)") (class "Default")
      (node (ref "U$2") (pin "90") (pinfunction "F4_90") (pintype "bidirectional"))
    )
    (net (code "167") (name "unconnected-(U$2-G1-Pad130)") (class "Default")
      (node (ref "U$2") (pin "130") (pinfunction "G1_130") (pintype "bidirectional"))
    )
    (net (code "168") (name "unconnected-(U$2-G2-Pad128)") (class "Default")
      (node (ref "U$2") (pin "128") (pinfunction "G2_128") (pintype "bidirectional"))
    )
    (net (code "169") (name "unconnected-(U$2-G3-Pad127)") (class "Default")
      (node (ref "U$2") (pin "127") (pinfunction "G3_127") (pintype "bidirectional"))
    )
    (net (code "170") (name "unconnected-(U$2-H2-Pad126)") (class "Default")
      (node (ref "U$2") (pin "126") (pinfunction "H2_126") (pintype "bidirectional"))
    )
    (net (code "171") (name "unconnected-(U$2-H3-Pad125)") (class "Default")
      (node (ref "U$2") (pin "125") (pinfunction "H3_125") (pintype "bidirectional"))
    )
    (net (code "172") (name "unconnected-(U$2-H5-Pad124)") (class "Default")
      (node (ref "U$2") (pin "124") (pinfunction "H5_124") (pintype "bidirectional"))
    )
    (net (code "173") (name "unconnected-(U$2-J1-Pad123)") (class "Default")
      (node (ref "U$2") (pin "123") (pinfunction "J1_123") (pintype "bidirectional"))
    )
    (net (code "174") (name "unconnected-(U$2-J2-Pad119)") (class "Default")
      (node (ref "U$2") (pin "119") (pinfunction "J2_119") (pintype "bidirectional"))
    )
    (net (code "175") (name "unconnected-(U$2-J4-Pad145)") (class "Default")
      (node (ref "U$2") (pin "145") (pinfunction "J4_145") (pintype "bidirectional"))
    )
    (net (code "176") (name "unconnected-(U$2-J5-Pad122)") (class "Default")
      (node (ref "U$2") (pin "122") (pinfunction "J5_122") (pintype "bidirectional"))
    )
    (net (code "177") (name "unconnected-(U$2-J6-Pad114)") (class "Default")
      (node (ref "U$2") (pin "114") (pinfunction "J6_114") (pintype "bidirectional"))
    )
    (net (code "178") (name "unconnected-(U$2-K1-Pad121)") (class "Default")
      (node (ref "U$2") (pin "121") (pinfunction "K1_121") (pintype "bidirectional"))
    )
    (net (code "179") (name "unconnected-(U$2-K2-Pad117)") (class "Default")
      (node (ref "U$2") (pin "117") (pinfunction "K2_117") (pintype "bidirectional"))
    )
    (net (code "180") (name "unconnected-(U$2-K3-Pad120)") (class "Default")
      (node (ref "U$2") (pin "120") (pinfunction "K3_120") (pintype "bidirectional"))
    )
    (net (code "181") (name "unconnected-(U$2-K4-Pad143)") (class "Default")
      (node (ref "U$2") (pin "143") (pinfunction "K4_143") (pintype "bidirectional"))
    )
    (net (code "182") (name "unconnected-(U$2-K6-Pad112)") (class "Default")
      (node (ref "U$2") (pin "112") (pinfunction "K6_112") (pintype "bidirectional"))
    )
    (net (code "183") (name "unconnected-(U$2-L1-Pad113)") (class "Default")
      (node (ref "U$2") (pin "113") (pinfunction "L1_113") (pintype "bidirectional"))
    )
    (net (code "184") (name "unconnected-(U$2-L3-Pad118)") (class "Default")
      (node (ref "U$2") (pin "118") (pinfunction "L3_118") (pintype "bidirectional"))
    )
    (net (code "185") (name "unconnected-(U$2-L5-Pad103)") (class "Default")
      (node (ref "U$2") (pin "103") (pinfunction "L5_103") (pintype "bidirectional"))
    )
    (net (code "186") (name "unconnected-(U$2-L6-Pad92)") (class "Default")
      (node (ref "U$2") (pin "92") (pinfunction "L6_92") (pintype "bidirectional"))
    )
    (net (code "187") (name "unconnected-(U$2-L10-Pad12)") (class "Default")
      (node (ref "U$2") (pin "12") (pinfunction "L10_12") (pintype "bidirectional"))
    )
    (net (code "188") (name "unconnected-(U$2-M1-Pad111)") (class "Default")
      (node (ref "U$2") (pin "111") (pinfunction "M1_111") (pintype "bidirectional"))
    )
    (net (code "189") (name "unconnected-(U$2-M2-Pad110)") (class "Default")
      (node (ref "U$2") (pin "110") (pinfunction "M2_110") (pintype "bidirectional"))
    )
    (net (code "190") (name "unconnected-(U$2-M3-Pad108)") (class "Default")
      (node (ref "U$2") (pin "108") (pinfunction "M3_108") (pintype "bidirectional"))
    )
    (net (code "191") (name "unconnected-(U$2-M9-Pad10)") (class "Default")
      (node (ref "U$2") (pin "10") (pinfunction "M9_10") (pintype "bidirectional"))
    )
    (net (code "192") (name "unconnected-(U$2-N2-Pad102)") (class "Default")
      (node (ref "U$2") (pin "102") (pinfunction "N2_102") (pintype "bidirectional"))
    )
    (net (code "193") (name "unconnected-(U$2-N5-Pad98)") (class "Default")
      (node (ref "U$2") (pin "98") (pinfunction "N5_98") (pintype "bidirectional"))
    )
    (net (code "194") (name "unconnected-(U$2-P1-Pad106)") (class "Default")
      (node (ref "U$2") (pin "106") (pinfunction "P1_106") (pintype "bidirectional"))
    )
    (net (code "195") (name "unconnected-(U$2-P2-Pad100)") (class "Default")
      (node (ref "U$2") (pin "100") (pinfunction "P2_100") (pintype "bidirectional"))
    )
    (net (code "196") (name "unconnected-(U$2-P6-Pad96)") (class "Default")
      (node (ref "U$2") (pin "96") (pinfunction "P6_96") (pintype "bidirectional"))
    )
    (net (code "197") (name "unconnected-(U$2-R1-Pad104)") (class "Default")
      (node (ref "U$2") (pin "104") (pinfunction "R1_104") (pintype "bidirectional"))
    )
    (net (code "198") (name "unconnected-(U$2-R2-Pad43)") (class "Default")
      (node (ref "U$2") (pin "43") (pinfunction "R2_43") (pintype "bidirectional"))
    )
    (net (code "199") (name "unconnected-(U$2-R3-Pad41)") (class "Default")
      (node (ref "U$2") (pin "41") (pinfunction "R3_41") (pintype "bidirectional"))
    )
    (net (code "200") (name "unconnected-(U$2-R4-Pad32)") (class "Default")
      (node (ref "U$2") (pin "32") (pinfunction "R4_32") (pintype "bidirectional"))
    )
    (net (code "201") (name "unconnected-(U$2-R6-Pad19)") (class "Default")
      (node (ref "U$2") (pin "19") (pinfunction "R6_19") (pintype "bidirectional"))
    )
    (net (code "202") (name "unconnected-(U$2-R13-Pad89)") (class "Default")
      (node (ref "U$2") (pin "89") (pinfunction "R13_89") (pintype "bidirectional"))
    )
    (net (code "203") (name "unconnected-(U$2-T4-Pad34)") (class "Default")
      (node (ref "U$2") (pin "34") (pinfunction "T4_34") (pintype "bidirectional"))
    )
    (net (code "204") (name "unconnected-(U$2-T5-Pad27)") (class "Default")
      (node (ref "U$2") (pin "27") (pinfunction "T5_27") (pintype "bidirectional"))
    )
    (net (code "205") (name "unconnected-(U$2-T6-Pad21)") (class "Default")
      (node (ref "U$2") (pin "21") (pinfunction "T6_21") (pintype "bidirectional"))
    )
    (net (code "206") (name "unconnected-(U$2-T13-Pad87)") (class "Default")
      (node (ref "U$2") (pin "87") (pinfunction "T13_87") (pintype "bidirectional"))
    )
    (net (code "207") (name "unconnected-(U$2-T14-Pad148)") (class "Default")
      (node (ref "U$2") (pin "148") (pinfunction "T14_148") (pintype "bidirectional"))
    )
    (net (code "208") (name "unconnected-(U$2-T16-Pad147)") (class "Default")
      (node (ref "U$2") (pin "147") (pinfunction "T16_147") (pintype "bidirectional"))
    )
    (net (code "209") (name "unconnected-(U$2-U2-Pad49)") (class "Default")
      (node (ref "U$2") (pin "49") (pinfunction "U2_49") (pintype "bidirectional"))
    )
    (net (code "210") (name "unconnected-(U$2-U3-Pad50)") (class "Default")
      (node (ref "U$2") (pin "50") (pinfunction "U3_50") (pintype "bidirectional"))
    )
    (net (code "211") (name "unconnected-(U$2-U5-Pad29)") (class "Default")
      (node (ref "U$2") (pin "29") (pinfunction "U5_29") (pintype "bidirectional"))
    )
    (net (code "212") (name "unconnected-(U$2-U6-Pad23)") (class "Default")
      (node (ref "U$2") (pin "23") (pinfunction "U6_23") (pintype "bidirectional"))
    )
    (net (code "213") (name "unconnected-(U$2-U13-Pad88)") (class "Default")
      (node (ref "U$2") (pin "88") (pinfunction "U13_88") (pintype "bidirectional"))
    )
    (net (code "214") (name "unconnected-(U$2-U15-Pad144)") (class "Default")
      (node (ref "U$2") (pin "144") (pinfunction "U15_144") (pintype "bidirectional"))
    )
    (net (code "215") (name "unconnected-(U$2-U16-Pad149)") (class "Default")
      (node (ref "U$2") (pin "149") (pinfunction "U16_149") (pintype "bidirectional"))
    )
    (net (code "216") (name "unconnected-(U$2-V2-Pad51)") (class "Default")
      (node (ref "U$2") (pin "51") (pinfunction "V2_51") (pintype "bidirectional"))
    )
    (net (code "217") (name "unconnected-(U$2-V3-Pad52)") (class "Default")
      (node (ref "U$2") (pin "52") (pinfunction "V3_52") (pintype "bidirectional"))
    )
    (net (code "218") (name "unconnected-(U$2-V5-Pad25)") (class "Default")
      (node (ref "U$2") (pin "25") (pinfunction "V5_25") (pintype "bidirectional"))
    )
    (net (code "219") (name "unconnected-(U$2-V12-Pad85)") (class "Default")
      (node (ref "U$2") (pin "85") (pinfunction "V12_85") (pintype "bidirectional"))
    )
    (net (code "220") (name "unconnected-(U$2-V13-Pad151)") (class "Default")
      (node (ref "U$2") (pin "151") (pinfunction "V13_151") (pintype "bidirectional"))
    )
    (net (code "221") (name "unconnected-(U$2-V15-Pad146)") (class "Default")
      (node (ref "U$2") (pin "146") (pinfunction "V15_146") (pintype "bidirectional"))
    )
    (net (code "222") (name "unconnected-(U$2-VCCO_MC1-Pad36)") (class "Default")
      (node (ref "U$2") (pin "36") (pinfunction "VCCO_MC1_36") (pintype "bidirectional"))
    )
    (net (code "223") (name "unconnected-(U$2-VCCO_MC1.1-Pad56)") (class "Default")
      (node (ref "U$2") (pin "56") (pinfunction "VCCO_MC1.1_56") (pintype "bidirectional"))
    )
    (net (code "224") (name "unconnected-(U$2-VCCO_MC2-Pad115)") (class "Default")
      (node (ref "U$2") (pin "115") (pinfunction "VCCO_MC2_115") (pintype "bidirectional"))
    )
    (net (code "225") (name "unconnected-(U$2-VCCO_MC2.1-Pad135)") (class "Default")
      (node (ref "U$2") (pin "135") (pinfunction "VCCO_MC2.1_135") (pintype "bidirectional"))
    )
    (net (code "226") (name "unconnected-(U$2-W1-Pad54)") (class "Default")
      (node (ref "U$2") (pin "54") (pinfunction "W1_54") (pintype "bidirectional"))
    )
    (net (code "227") (name "unconnected-(U$2-W2-Pad53)") (class "Default")
      (node (ref "U$2") (pin "53") (pinfunction "W2_53") (pintype "bidirectional"))
    )
    (net (code "228") (name "unconnected-(U$2-W9-Pad15)") (class "Default")
      (node (ref "U$2") (pin "15") (pinfunction "W9_15") (pintype "bidirectional"))
    )
    (net (code "229") (name "unconnected-(U$2-W15-Pad72)") (class "Default")
      (node (ref "U$2") (pin "72") (pinfunction "W15_72") (pintype "bidirectional"))
    )
    (net (code "230") (name "unconnected-(U$2-W16-Pad74)") (class "Default")
      (node (ref "U$2") (pin "74") (pinfunction "W16_74") (pintype "bidirectional"))
    )
    (net (code "231") (name "unconnected-(U$2-Y1-Pad58)") (class "Default")
      (node (ref "U$2") (pin "58") (pinfunction "Y1_58") (pintype "bidirectional"))
    )
    (net (code "232") (name "unconnected-(U$2-Y2-Pad57)") (class "Default")
      (node (ref "U$2") (pin "57") (pinfunction "Y2_57") (pintype "bidirectional"))
    )
    (net (code "233") (name "unconnected-(U$2-Y3-Pad45)") (class "Default")
      (node (ref "U$2") (pin "45") (pinfunction "Y3_45") (pintype "bidirectional"))
    )
    (net (code "234") (name "unconnected-(U$2-Y4-Pad38)") (class "Default")
      (node (ref "U$2") (pin "38") (pinfunction "Y4_38") (pintype "bidirectional"))
    )
    (net (code "235") (name "unconnected-(U$2-Y6-Pad42)") (class "Default")
      (node (ref "U$2") (pin "42") (pinfunction "Y6_42") (pintype "bidirectional"))
    )
    (net (code "236") (name "unconnected-(U$2-Y8-Pad24)") (class "Default")
      (node (ref "U$2") (pin "24") (pinfunction "Y8_24") (pintype "bidirectional"))
    )
    (net (code "237") (name "unconnected-(U$2-Y9-Pad17)") (class "Default")
      (node (ref "U$2") (pin "17") (pinfunction "Y9_17") (pintype "bidirectional"))
    )
    (net (code "238") (name "unconnected-(U$2-Y13-Pad64)") (class "Default")
      (node (ref "U$2") (pin "64") (pinfunction "Y13_64") (pintype "bidirectional"))
    )
    (net (code "239") (name "unconnected-(U$2-Y16-Pad75)") (class "Default")
      (node (ref "U$2") (pin "75") (pinfunction "Y16_75") (pintype "bidirectional"))
    )
    (net (code "240") (name "unconnected-(U1-BW-Pad1)") (class "Default")
      (node (ref "U1") (pin "1") (pinfunction "BW_1") (pintype "bidirectional"))
    )
    (net (code "241") (name "unconnected-(U2-BW-Pad1)") (class "Default")
      (node (ref "U2") (pin "1") (pinfunction "BW_1") (pintype "bidirectional"))
    )
  )
)
